# board1-0.net
KiCad netlist of a schematic drawn in EAGLE
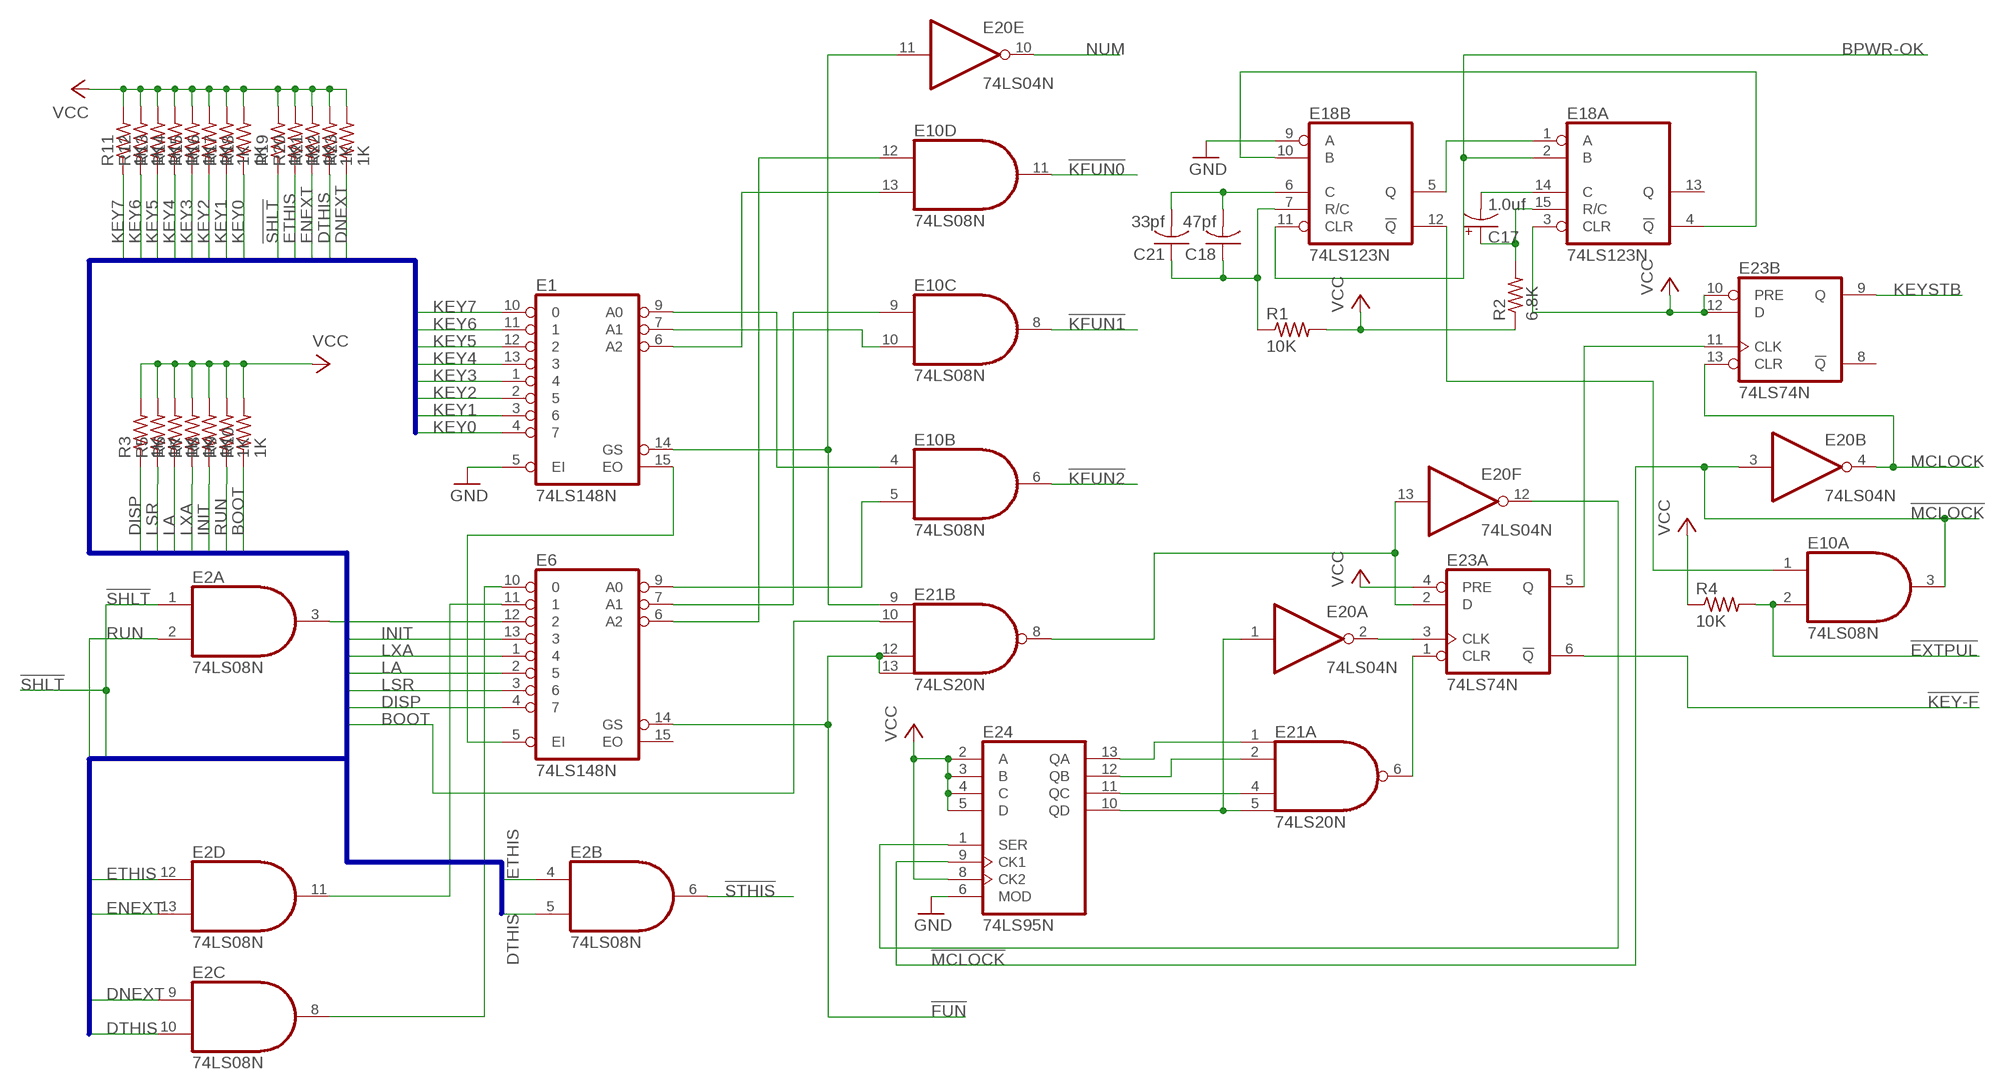
[diagram p0: schematic, sheet 1]
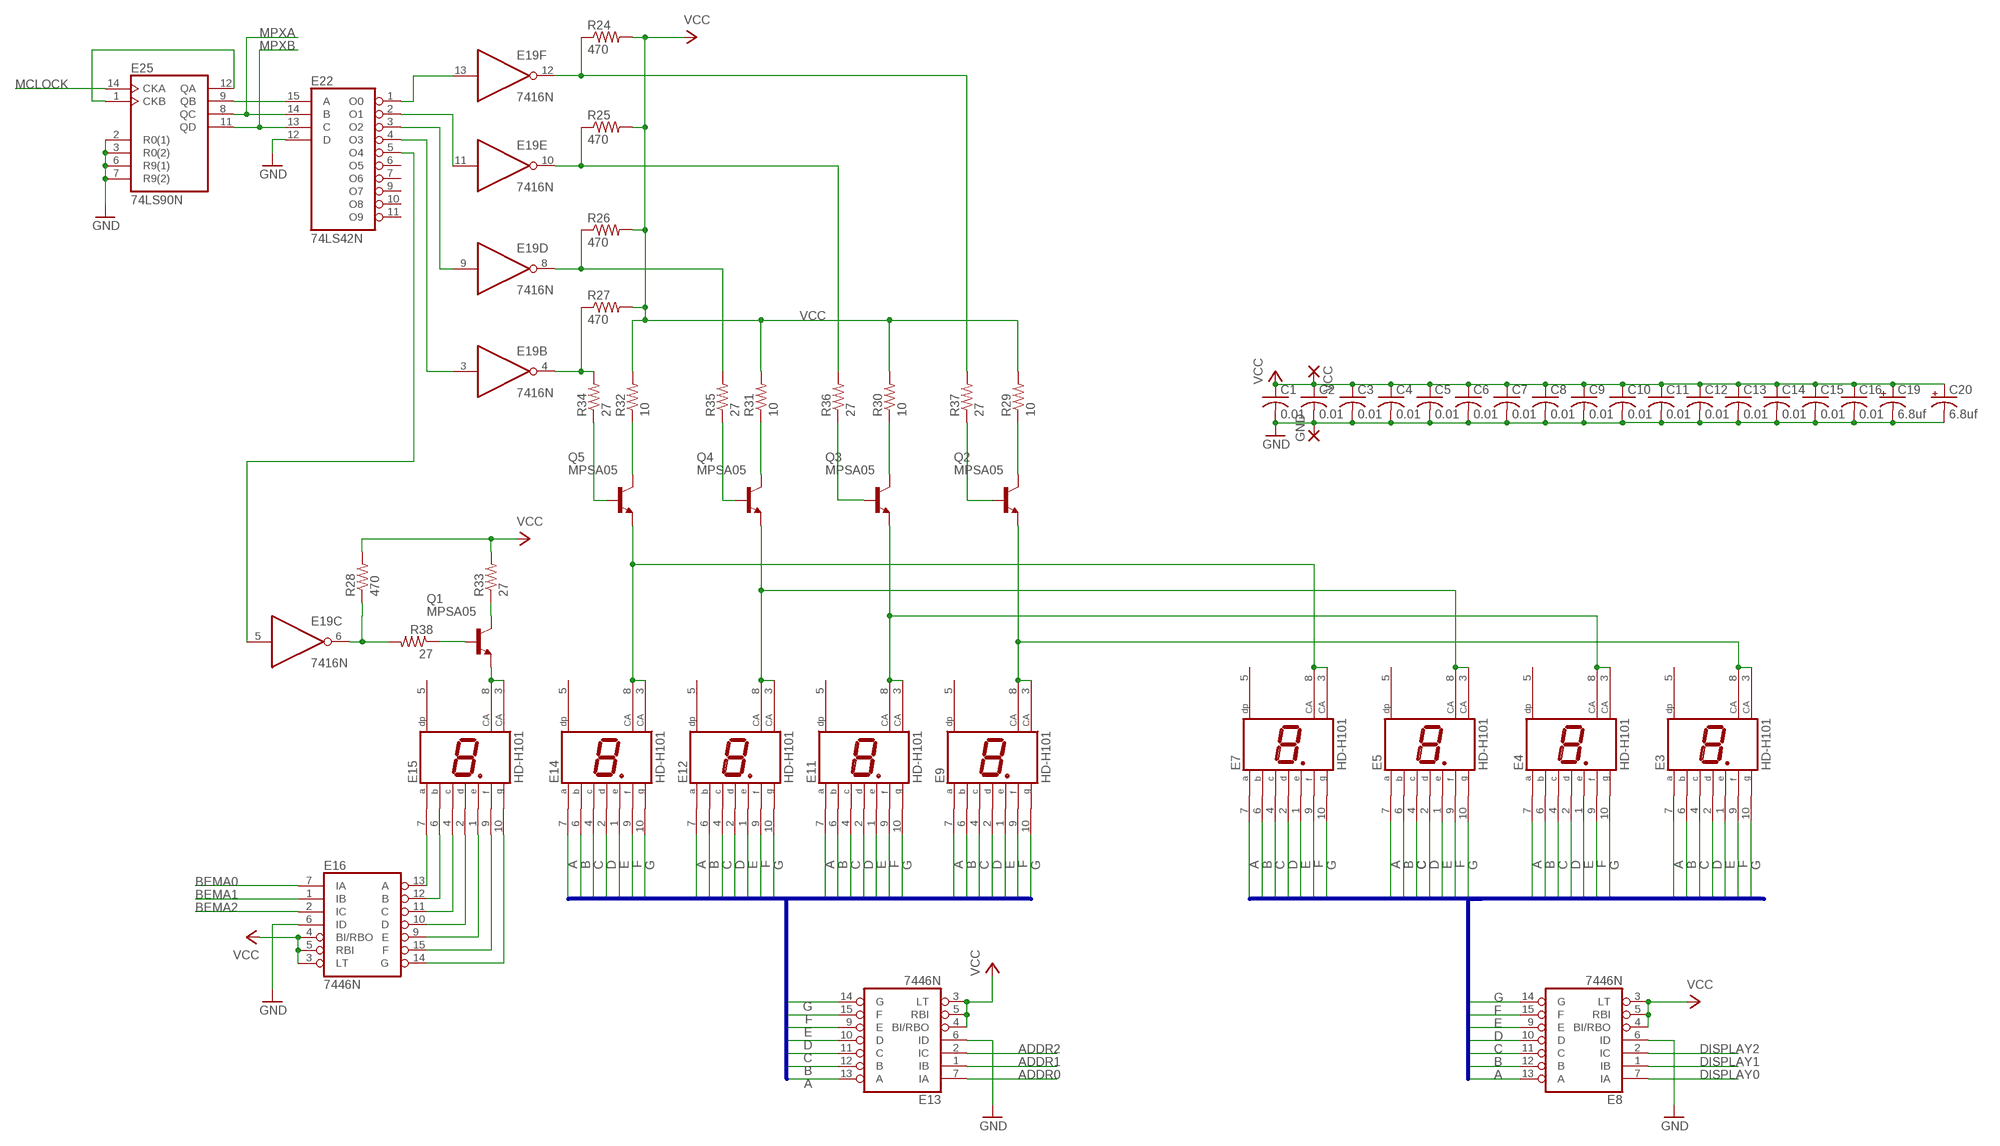
[diagram p1: schematic, sheet 2]
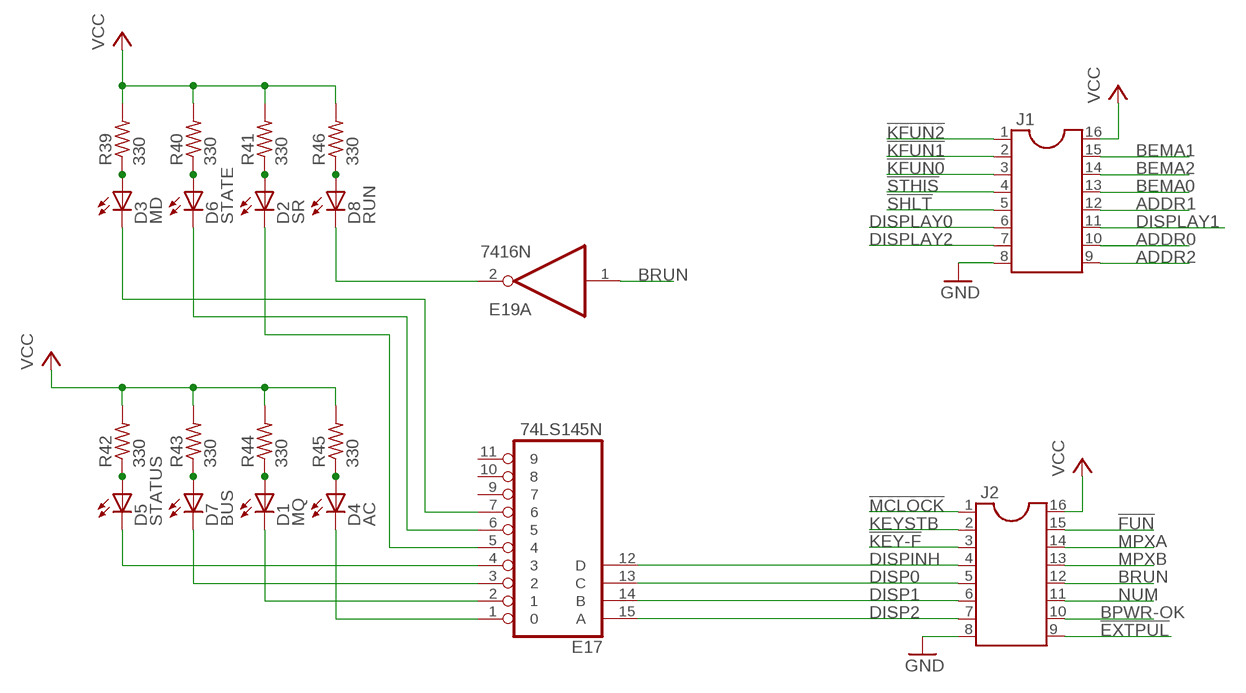
[diagram p2: schematic, sheet 3]
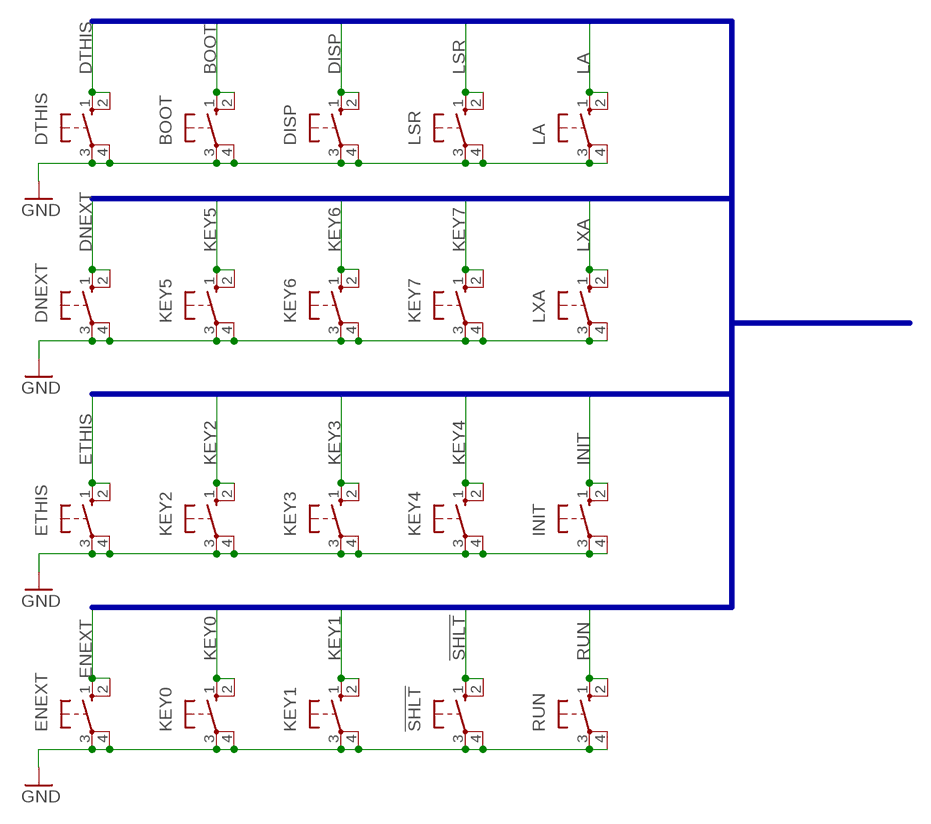
[diagram p3: schematic, sheet 4]

(export (version "E")
  (design (tool "Eeschema 10.0.6"))
  (components
    (comp (ref "!SHLT")
      (value "40-XX")
      (footprint "eagle-import:B3F-40XX")
      (fields (field (name "MF") "OMRON COMPONENTS USA") (field (name "MPN") "B3F-4000"))
      (libsource (lib "eagle-import") (part "40-XX"))
    )
    (comp (ref "BOOT")
      (value "40-XX")
      (footprint "eagle-import:B3F-40XX")
      (fields (field (name "MF") "OMRON COMPONENTS USA") (field (name "MPN") "B3F-4000"))
      (libsource (lib "eagle-import") (part "40-XX"))
    )
    (comp (ref "DISP")
      (value "40-XX")
      (footprint "eagle-import:B3F-40XX")
      (fields (field (name "MF") "OMRON COMPONENTS USA") (field (name "MPN") "B3F-4000"))
      (libsource (lib "eagle-import") (part "40-XX"))
    )
    (comp (ref "DNEXT")
      (value "40-XX")
      (footprint "eagle-import:B3F-40XX")
      (fields (field (name "MF") "OMRON COMPONENTS USA") (field (name "MPN") "B3F-4000"))
      (libsource (lib "eagle-import") (part "40-XX"))
    )
    (comp (ref "DTHIS")
      (value "40-XX")
      (footprint "eagle-import:B3F-40XX")
      (fields (field (name "MF") "OMRON COMPONENTS USA") (field (name "MPN") "B3F-4000"))
      (libsource (lib "eagle-import") (part "40-XX"))
    )
    (comp (ref "ENEXT")
      (value "40-XX")
      (footprint "eagle-import:B3F-40XX")
      (fields (field (name "MF") "OMRON COMPONENTS USA") (field (name "MPN") "B3F-4000"))
      (libsource (lib "eagle-import") (part "40-XX"))
    )
    (comp (ref "ETHIS")
      (value "40-XX")
      (footprint "eagle-import:B3F-40XX")
      (fields (field (name "MF") "OMRON COMPONENTS USA") (field (name "MPN") "B3F-4000"))
      (libsource (lib "eagle-import") (part "40-XX"))
    )
    (comp (ref "INIT")
      (value "40-XX")
      (footprint "eagle-import:B3F-40XX")
      (fields (field (name "MF") "OMRON COMPONENTS USA") (field (name "MPN") "B3F-4000"))
      (libsource (lib "eagle-import") (part "40-XX"))
    )
    (comp (ref "KEY0")
      (value "40-XX")
      (footprint "eagle-import:B3F-40XX")
      (fields (field (name "MF") "OMRON COMPONENTS USA") (field (name "MPN") "B3F-4000"))
      (libsource (lib "eagle-import") (part "40-XX"))
    )
    (comp (ref "KEY1")
      (value "40-XX")
      (footprint "eagle-import:B3F-40XX")
      (fields (field (name "MF") "OMRON COMPONENTS USA") (field (name "MPN") "B3F-4000"))
      (libsource (lib "eagle-import") (part "40-XX"))
    )
    (comp (ref "KEY2")
      (value "40-XX")
      (footprint "eagle-import:B3F-40XX")
      (fields (field (name "MF") "OMRON COMPONENTS USA") (field (name "MPN") "B3F-4000"))
      (libsource (lib "eagle-import") (part "40-XX"))
    )
    (comp (ref "KEY3")
      (value "40-XX")
      (footprint "eagle-import:B3F-40XX")
      (fields (field (name "MF") "OMRON COMPONENTS USA") (field (name "MPN") "B3F-4000"))
      (libsource (lib "eagle-import") (part "40-XX"))
    )
    (comp (ref "KEY4")
      (value "40-XX")
      (footprint "eagle-import:B3F-40XX")
      (fields (field (name "MF") "OMRON COMPONENTS USA") (field (name "MPN") "B3F-4000"))
      (libsource (lib "eagle-import") (part "40-XX"))
    )
    (comp (ref "KEY5")
      (value "40-XX")
      (footprint "eagle-import:B3F-40XX")
      (fields (field (name "MF") "OMRON COMPONENTS USA") (field (name "MPN") "B3F-4000"))
      (libsource (lib "eagle-import") (part "40-XX"))
    )
    (comp (ref "KEY6")
      (value "40-XX")
      (footprint "eagle-import:B3F-40XX")
      (fields (field (name "MF") "OMRON COMPONENTS USA") (field (name "MPN") "B3F-4000"))
      (libsource (lib "eagle-import") (part "40-XX"))
    )
    (comp (ref "KEY7")
      (value "40-XX")
      (footprint "eagle-import:B3F-40XX")
      (fields (field (name "MF") "OMRON COMPONENTS USA") (field (name "MPN") "B3F-4000"))
      (libsource (lib "eagle-import") (part "40-XX"))
    )
    (comp (ref "LA")
      (value "40-XX")
      (footprint "eagle-import:B3F-40XX")
      (fields (field (name "MF") "OMRON COMPONENTS USA") (field (name "MPN") "B3F-4000"))
      (libsource (lib "eagle-import") (part "40-XX"))
    )
    (comp (ref "LSR")
      (value "40-XX")
      (footprint "eagle-import:B3F-40XX")
      (fields (field (name "MF") "OMRON COMPONENTS USA") (field (name "MPN") "B3F-4000"))
      (libsource (lib "eagle-import") (part "40-XX"))
    )
    (comp (ref "LXA")
      (value "40-XX")
      (footprint "eagle-import:B3F-40XX")
      (fields (field (name "MF") "OMRON COMPONENTS USA") (field (name "MPN") "B3F-4000"))
      (libsource (lib "eagle-import") (part "40-XX"))
    )
    (comp (ref "RUN")
      (value "40-XX")
      (footprint "eagle-import:B3F-40XX")
      (fields (field (name "MF") "OMRON COMPONENTS USA") (field (name "MPN") "B3F-4000"))
      (libsource (lib "eagle-import") (part "40-XX"))
    )
    (comp (ref "D1")
      (value "MQ")
      (footprint "eagle-import:LED5MM")
      (libsource (lib "eagle-import") (part "LED5MM"))
    )
    (comp (ref "D2")
      (value "SR")
      (footprint "eagle-import:LED5MM")
      (libsource (lib "eagle-import") (part "LED5MM"))
    )
    (comp (ref "D3")
      (value "MD")
      (footprint "eagle-import:LED5MM")
      (libsource (lib "eagle-import") (part "LED5MM"))
    )
    (comp (ref "D4")
      (value "AC")
      (footprint "eagle-import:LED5MM")
      (libsource (lib "eagle-import") (part "LED5MM"))
    )
    (comp (ref "D5")
      (value "STATUS")
      (footprint "eagle-import:LED5MM")
      (libsource (lib "eagle-import") (part "LED5MM"))
    )
    (comp (ref "D6")
      (value "STATE")
      (footprint "eagle-import:LED5MM")
      (libsource (lib "eagle-import") (part "LED5MM"))
    )
    (comp (ref "D7")
      (value "BUS")
      (footprint "eagle-import:LED5MM")
      (libsource (lib "eagle-import") (part "LED5MM"))
    )
    (comp (ref "D8")
      (value "RUN")
      (footprint "eagle-import:LED5MM")
      (libsource (lib "eagle-import") (part "LED5MM"))
    )
    (comp (ref "E17")
      (value "74LS145N")
      (footprint "eagle-import:DIL16")
      (libsource (lib "eagle-import") (part "74145NLS"))
    )
    (comp (ref "E19")
      (value "7416N")
      (footprint "eagle-import:DIL14")
      (libsource (lib "eagle-import") (part "7416N"))
    )
    (comp (ref "J1")
      (value "DIL16S")
      (footprint "eagle-import:SOCKET-16")
      (libsource (lib "eagle-import") (part "DIL16S"))
    )
    (comp (ref "J2")
      (value "DIL16S")
      (footprint "eagle-import:SOCKET-16")
      (libsource (lib "eagle-import") (part "DIL16S"))
    )
    (comp (ref "R39")
      (value "330")
      (footprint "eagle-import:0207_10")
      (libsource (lib "eagle-import") (part "R-US_0207/10"))
    )
    (comp (ref "R40")
      (value "330")
      (footprint "eagle-import:0207_10")
      (libsource (lib "eagle-import") (part "R-US_0207/10"))
    )
    (comp (ref "R41")
      (value "330")
      (footprint "eagle-import:0207_10")
      (libsource (lib "eagle-import") (part "R-US_0207/10"))
    )
    (comp (ref "R42")
      (value "330")
      (footprint "eagle-import:0207_10")
      (libsource (lib "eagle-import") (part "R-US_0207/10"))
    )
    (comp (ref "R43")
      (value "330")
      (footprint "eagle-import:0207_10")
      (libsource (lib "eagle-import") (part "R-US_0207/10"))
    )
    (comp (ref "R44")
      (value "330")
      (footprint "eagle-import:0207_10")
      (libsource (lib "eagle-import") (part "R-US_0207/10"))
    )
    (comp (ref "R45")
      (value "330")
      (footprint "eagle-import:0207_10")
      (libsource (lib "eagle-import") (part "R-US_0207/10"))
    )
    (comp (ref "R46")
      (value "330")
      (footprint "eagle-import:0207_10")
      (libsource (lib "eagle-import") (part "R-US_0207/10"))
    )
    (comp (ref "C17")
      (value "1.0uf")
      (footprint "eagle-import:E15-5")
      (libsource (lib "eagle-import") (part "CPOL-USE15-5AXIAL"))
    )
    (comp (ref "C18")
      (value "47pf")
      (footprint "eagle-import:C050-025X075")
      (libsource (lib "eagle-import") (part "C-US050-025X075"))
    )
    (comp (ref "C21")
      (value "33pf")
      (footprint "eagle-import:C050-025X075")
      (libsource (lib "eagle-import") (part "C-US050-025X075"))
    )
    (comp (ref "E1")
      (value "74LS148N")
      (footprint "eagle-import:DIL16")
      (libsource (lib "eagle-import") (part "74148NLS"))
    )
    (comp (ref "E2")
      (value "74LS08N")
      (footprint "eagle-import:DIL14")
      (libsource (lib "eagle-import") (part "7408NLS"))
    )
    (comp (ref "E6")
      (value "74LS148N")
      (footprint "eagle-import:DIL16")
      (libsource (lib "eagle-import") (part "74148NLS"))
    )
    (comp (ref "E10")
      (value "74LS08N")
      (footprint "eagle-import:DIL14")
      (libsource (lib "eagle-import") (part "7408NLS"))
    )
    (comp (ref "E18")
      (value "74LS123N")
      (footprint "eagle-import:DIL16")
      (libsource (lib "eagle-import") (part "74123NLS"))
    )
    (comp (ref "E20")
      (value "74LS04N")
      (footprint "eagle-import:DIL14")
      (libsource (lib "eagle-import") (part "7404NLS"))
    )
    (comp (ref "E21")
      (value "74LS20N")
      (footprint "eagle-import:DIL14")
      (libsource (lib "eagle-import") (part "7420NLS"))
    )
    (comp (ref "E23")
      (value "74LS74N")
      (footprint "eagle-import:DIL14")
      (libsource (lib "eagle-import") (part "7474NLS"))
    )
    (comp (ref "E24")
      (value "74LS95N")
      (footprint "eagle-import:DIL14")
      (libsource (lib "eagle-import") (part "7495NLS"))
    )
    (comp (ref "R1")
      (value "10K")
      (footprint "eagle-import:0207_10")
      (libsource (lib "eagle-import") (part "R-US_0207/10"))
    )
    (comp (ref "R2")
      (value "6.8K")
      (footprint "eagle-import:0207_10")
      (libsource (lib "eagle-import") (part "R-US_0207/10"))
    )
    (comp (ref "R3")
      (value "1K")
      (footprint "eagle-import:0207_10")
      (libsource (lib "eagle-import") (part "R-US_0207/10"))
    )
    (comp (ref "R4")
      (value "10K")
      (footprint "eagle-import:0207_10")
      (libsource (lib "eagle-import") (part "R-US_0207/10"))
    )
    (comp (ref "R5")
      (value "1K")
      (footprint "eagle-import:0207_10")
      (libsource (lib "eagle-import") (part "R-US_0207/10"))
    )
    (comp (ref "R6")
      (value "1K")
      (footprint "eagle-import:0207_10")
      (libsource (lib "eagle-import") (part "R-US_0207/10"))
    )
    (comp (ref "R7")
      (value "1K")
      (footprint "eagle-import:0207_10")
      (libsource (lib "eagle-import") (part "R-US_0207/10"))
    )
    (comp (ref "R8")
      (value "1K")
      (footprint "eagle-import:0207_10")
      (libsource (lib "eagle-import") (part "R-US_0207/10"))
    )
    (comp (ref "R9")
      (value "1K")
      (footprint "eagle-import:0207_10")
      (libsource (lib "eagle-import") (part "R-US_0207/10"))
    )
    (comp (ref "R10")
      (value "1K")
      (footprint "eagle-import:0207_10")
      (libsource (lib "eagle-import") (part "R-US_0207/10"))
    )
    (comp (ref "R11")
      (value "1K")
      (footprint "eagle-import:0207_10")
      (libsource (lib "eagle-import") (part "R-US_0207/10"))
    )
    (comp (ref "R12")
      (value "1K")
      (footprint "eagle-import:0207_10")
      (libsource (lib "eagle-import") (part "R-US_0207/10"))
    )
    (comp (ref "R13")
      (value "1K")
      (footprint "eagle-import:0207_10")
      (libsource (lib "eagle-import") (part "R-US_0207/10"))
    )
    (comp (ref "R14")
      (value "1K")
      (footprint "eagle-import:0207_10")
      (libsource (lib "eagle-import") (part "R-US_0207/10"))
    )
    (comp (ref "R15")
      (value "1K")
      (footprint "eagle-import:0207_10")
      (libsource (lib "eagle-import") (part "R-US_0207/10"))
    )
    (comp (ref "R16")
      (value "1K")
      (footprint "eagle-import:0207_10")
      (libsource (lib "eagle-import") (part "R-US_0207/10"))
    )
    (comp (ref "R17")
      (value "1K")
      (footprint "eagle-import:0207_10")
      (libsource (lib "eagle-import") (part "R-US_0207/10"))
    )
    (comp (ref "R18")
      (value "1K")
      (footprint "eagle-import:0207_10")
      (libsource (lib "eagle-import") (part "R-US_0207/10"))
    )
    (comp (ref "R19")
      (value "1K")
      (footprint "eagle-import:0207_10")
      (libsource (lib "eagle-import") (part "R-US_0207/10"))
    )
    (comp (ref "R20")
      (value "1K")
      (footprint "eagle-import:0207_10")
      (libsource (lib "eagle-import") (part "R-US_0207/10"))
    )
    (comp (ref "R21")
      (value "1K")
      (footprint "eagle-import:0207_10")
      (libsource (lib "eagle-import") (part "R-US_0207/10"))
    )
    (comp (ref "R22")
      (value "1K")
      (footprint "eagle-import:0207_10")
      (libsource (lib "eagle-import") (part "R-US_0207/10"))
    )
    (comp (ref "R23")
      (value "1K")
      (footprint "eagle-import:0207_10")
      (libsource (lib "eagle-import") (part "R-US_0207/10"))
    )
    (comp (ref "C1")
      (value "0.01")
      (footprint "eagle-import:C050-025X075")
      (libsource (lib "eagle-import") (part "C-US050-025X075"))
    )
    (comp (ref "C2")
      (value "0.01")
      (footprint "eagle-import:C050-025X075")
      (libsource (lib "eagle-import") (part "C-US050-025X075"))
    )
    (comp (ref "C3")
      (value "0.01")
      (footprint "eagle-import:C050-025X075")
      (libsource (lib "eagle-import") (part "C-US050-025X075"))
    )
    (comp (ref "C4")
      (value "0.01")
      (footprint "eagle-import:C050-025X075")
      (libsource (lib "eagle-import") (part "C-US050-025X075"))
    )
    (comp (ref "C5")
      (value "0.01")
      (footprint "eagle-import:C050-025X075")
      (libsource (lib "eagle-import") (part "C-US050-025X075"))
    )
    (comp (ref "C6")
      (value "0.01")
      (footprint "eagle-import:C050-025X075")
      (libsource (lib "eagle-import") (part "C-US050-025X075"))
    )
    (comp (ref "C7")
      (value "0.01")
      (footprint "eagle-import:C050-025X075")
      (libsource (lib "eagle-import") (part "C-US050-025X075"))
    )
    (comp (ref "C8")
      (value "0.01")
      (footprint "eagle-import:C050-025X075")
      (libsource (lib "eagle-import") (part "C-US050-025X075"))
    )
    (comp (ref "C9")
      (value "0.01")
      (footprint "eagle-import:C050-025X075")
      (libsource (lib "eagle-import") (part "C-US050-025X075"))
    )
    (comp (ref "C10")
      (value "0.01")
      (footprint "eagle-import:C050-025X075")
      (libsource (lib "eagle-import") (part "C-US050-025X075"))
    )
    (comp (ref "C11")
      (value "0.01")
      (footprint "eagle-import:C050-025X075")
      (libsource (lib "eagle-import") (part "C-US050-025X075"))
    )
    (comp (ref "C12")
      (value "0.01")
      (footprint "eagle-import:C050-025X075")
      (libsource (lib "eagle-import") (part "C-US050-025X075"))
    )
    (comp (ref "C13")
      (value "0.01")
      (footprint "eagle-import:C050-025X075")
      (libsource (lib "eagle-import") (part "C-US050-025X075"))
    )
    (comp (ref "C14")
      (value "0.01")
      (footprint "eagle-import:C050-025X075")
      (libsource (lib "eagle-import") (part "C-US050-025X075"))
    )
    (comp (ref "C15")
      (value "0.01")
      (footprint "eagle-import:C050-025X075")
      (libsource (lib "eagle-import") (part "C-US050-025X075"))
    )
    (comp (ref "C16")
      (value "0.01")
      (footprint "eagle-import:C050-025X075")
      (libsource (lib "eagle-import") (part "C-US050-025X075"))
    )
    (comp (ref "C19")
      (value "6.8uf")
      (footprint "eagle-import:E22-6")
      (libsource (lib "eagle-import") (part "CPOL-USE22-6AXIAL"))
    )
    (comp (ref "C20")
      (value "6.8uf")
      (footprint "eagle-import:E22-6")
      (libsource (lib "eagle-import") (part "CPOL-USE22-6AXIAL"))
    )
    (comp (ref "E3")
      (value "HD-H101")
      (footprint "eagle-import:HDSP-M")
      (libsource (lib "eagle-import") (part "HD-H101"))
    )
    (comp (ref "E4")
      (value "HD-H101")
      (footprint "eagle-import:HDSP-M")
      (libsource (lib "eagle-import") (part "HD-H101"))
    )
    (comp (ref "E5")
      (value "HD-H101")
      (footprint "eagle-import:HDSP-M")
      (libsource (lib "eagle-import") (part "HD-H101"))
    )
    (comp (ref "E7")
      (value "HD-H101")
      (footprint "eagle-import:HDSP-M")
      (libsource (lib "eagle-import") (part "HD-H101"))
    )
    (comp (ref "E8")
      (value "7446N")
      (footprint "eagle-import:DIL16")
      (libsource (lib "eagle-import") (part "7446N"))
    )
    (comp (ref "E9")
      (value "HD-H101")
      (footprint "eagle-import:HDSP-M")
      (libsource (lib "eagle-import") (part "HD-H101"))
    )
    (comp (ref "E11")
      (value "HD-H101")
      (footprint "eagle-import:HDSP-M")
      (libsource (lib "eagle-import") (part "HD-H101"))
    )
    (comp (ref "E12")
      (value "HD-H101")
      (footprint "eagle-import:HDSP-M")
      (libsource (lib "eagle-import") (part "HD-H101"))
    )
    (comp (ref "E13")
      (value "7446N")
      (footprint "eagle-import:DIL16")
      (libsource (lib "eagle-import") (part "7446N"))
    )
    (comp (ref "E14")
      (value "HD-H101")
      (footprint "eagle-import:HDSP-M")
      (libsource (lib "eagle-import") (part "HD-H101"))
    )
    (comp (ref "E15")
      (value "HD-H101")
      (footprint "eagle-import:HDSP-M")
      (libsource (lib "eagle-import") (part "HD-H101"))
    )
    (comp (ref "E16")
      (value "7446N")
      (footprint "eagle-import:DIL16")
      (libsource (lib "eagle-import") (part "7446N"))
    )
    (comp (ref "E22")
      (value "74LS42N")
      (footprint "eagle-import:DIL16")
      (libsource (lib "eagle-import") (part "7442NLS"))
    )
    (comp (ref "E25")
      (value "74LS90N")
      (footprint "eagle-import:DIL14")
      (libsource (lib "eagle-import") (part "7490NLS"))
    )
    (comp (ref "GND")
      (value "3,81/1,4")
      (footprint "eagle-import:3,81_1,4")
      (libsource (lib "eagle-import") (part "3,81/1,4"))
    )
    (comp (ref "Q1")
      (value "MPSA05")
      (footprint "eagle-import:TO18")
      (libsource (lib "eagle-import") (part "2N2222A"))
    )
    (comp (ref "Q2")
      (value "MPSA05")
      (footprint "eagle-import:TO18")
      (libsource (lib "eagle-import") (part "2N2222A"))
    )
    (comp (ref "Q3")
      (value "MPSA05")
      (footprint "eagle-import:TO18")
      (libsource (lib "eagle-import") (part "2N2222A"))
    )
    (comp (ref "Q4")
      (value "MPSA05")
      (footprint "eagle-import:TO18")
      (libsource (lib "eagle-import") (part "2N2222A"))
    )
    (comp (ref "Q5")
      (value "MPSA05")
      (footprint "eagle-import:TO18")
      (libsource (lib "eagle-import") (part "2N2222A"))
    )
    (comp (ref "R24")
      (value "470")
      (footprint "eagle-import:0207_10")
      (libsource (lib "eagle-import") (part "R-US_0207/10"))
    )
    (comp (ref "R25")
      (value "470")
      (footprint "eagle-import:0207_10")
      (libsource (lib "eagle-import") (part "R-US_0207/10"))
    )
    (comp (ref "R26")
      (value "470")
      (footprint "eagle-import:0207_10")
      (libsource (lib "eagle-import") (part "R-US_0207/10"))
    )
    (comp (ref "R27")
      (value "470")
      (footprint "eagle-import:0207_10")
      (libsource (lib "eagle-import") (part "R-US_0207/10"))
    )
    (comp (ref "R28")
      (value "470")
      (footprint "eagle-import:0207_10")
      (libsource (lib "eagle-import") (part "R-US_0207/10"))
    )
    (comp (ref "R29")
      (value "10")
      (footprint "eagle-import:0207_10")
      (libsource (lib "eagle-import") (part "R-US_0207/10"))
    )
    (comp (ref "R30")
      (value "10")
      (footprint "eagle-import:0207_10")
      (libsource (lib "eagle-import") (part "R-US_0207/10"))
    )
    (comp (ref "R31")
      (value "10")
      (footprint "eagle-import:0207_10")
      (libsource (lib "eagle-import") (part "R-US_0207/10"))
    )
    (comp (ref "R32")
      (value "10")
      (footprint "eagle-import:0207_10")
      (libsource (lib "eagle-import") (part "R-US_0207/10"))
    )
    (comp (ref "R33")
      (value "27")
      (footprint "eagle-import:0207_10")
      (libsource (lib "eagle-import") (part "R-US_0207/10"))
    )
    (comp (ref "R34")
      (value "27")
      (footprint "eagle-import:0207_10")
      (libsource (lib "eagle-import") (part "R-US_0207/10"))
    )
    (comp (ref "R35")
      (value "27")
      (footprint "eagle-import:0207_10")
      (libsource (lib "eagle-import") (part "R-US_0207/10"))
    )
    (comp (ref "R36")
      (value "27")
      (footprint "eagle-import:0207_10")
      (libsource (lib "eagle-import") (part "R-US_0207/10"))
    )
    (comp (ref "R37")
      (value "27")
      (footprint "eagle-import:0207_10")
      (libsource (lib "eagle-import") (part "R-US_0207/10"))
    )
    (comp (ref "R38")
      (value "27")
      (footprint "eagle-import:0207_10")
      (libsource (lib "eagle-import") (part "R-US_0207/10"))
    )
    (comp (ref "VCC")
      (value "3,81/1,4")
      (footprint "eagle-import:3,81_1,4")
      (libsource (lib "eagle-import") (part "3,81/1,4"))
    )
  )
  (nets
    (net (code "1") (name "A") (class "Default")
      (node (ref "E11") (pin "7") (pinfunction "A_7") (pintype "passive"))
      (node (ref "E12") (pin "7") (pinfunction "A_7") (pintype "passive"))
      (node (ref "E13") (pin "13") (pinfunction "A_13") (pintype "open_collector"))
      (node (ref "E14") (pin "7") (pinfunction "A_7") (pintype "passive"))
      (node (ref "E3") (pin "7") (pinfunction "A_7") (pintype "passive"))
      (node (ref "E4") (pin "7") (pinfunction "A_7") (pintype "passive"))
      (node (ref "E5") (pin "7") (pinfunction "A_7") (pintype "passive"))
      (node (ref "E7") (pin "7") (pinfunction "A_7") (pintype "passive"))
      (node (ref "E8") (pin "13") (pinfunction "A_13") (pintype "open_collector"))
      (node (ref "E9") (pin "7") (pinfunction "A_7") (pintype "passive"))
    )
    (net (code "2") (name "ADDR0") (class "Default")
      (node (ref "E13") (pin "7") (pinfunction "IA_7") (pintype "input"))
      (node (ref "J1") (pin "10") (pinfunction "10_10") (pintype "passive"))
    )
    (net (code "3") (name "ADDR1") (class "Default")
      (node (ref "E13") (pin "1") (pinfunction "IB_1") (pintype "input"))
      (node (ref "J1") (pin "12") (pinfunction "12_12") (pintype "passive"))
    )
    (net (code "4") (name "ADDR2") (class "Default")
      (node (ref "E13") (pin "2") (pinfunction "IC_2") (pintype "input"))
      (node (ref "J1") (pin "9") (pinfunction "9_9") (pintype "passive"))
    )
    (net (code "5") (name "B") (class "Default")
      (node (ref "E11") (pin "6") (pinfunction "B_6") (pintype "passive"))
      (node (ref "E12") (pin "6") (pinfunction "B_6") (pintype "passive"))
      (node (ref "E13") (pin "12") (pinfunction "B_12") (pintype "open_collector"))
      (node (ref "E14") (pin "6") (pinfunction "B_6") (pintype "passive"))
      (node (ref "E3") (pin "6") (pinfunction "B_6") (pintype "passive"))
      (node (ref "E4") (pin "6") (pinfunction "B_6") (pintype "passive"))
      (node (ref "E5") (pin "6") (pinfunction "B_6") (pintype "passive"))
      (node (ref "E7") (pin "6") (pinfunction "B_6") (pintype "passive"))
      (node (ref "E8") (pin "12") (pinfunction "B_12") (pintype "open_collector"))
      (node (ref "E9") (pin "6") (pinfunction "B_6") (pintype "passive"))
    )
    (net (code "6") (name "BEMA0") (class "Default")
      (node (ref "E16") (pin "7") (pinfunction "IA_7") (pintype "input"))
      (node (ref "J1") (pin "13") (pinfunction "13_13") (pintype "passive"))
    )
    (net (code "7") (name "BEMA1") (class "Default")
      (node (ref "E16") (pin "1") (pinfunction "IB_1") (pintype "input"))
      (node (ref "J1") (pin "15") (pinfunction "15_15") (pintype "passive"))
    )
    (net (code "8") (name "BEMA2") (class "Default")
      (node (ref "E16") (pin "2") (pinfunction "IC_2") (pintype "input"))
      (node (ref "J1") (pin "14") (pinfunction "14_14") (pintype "passive"))
    )
    (net (code "9") (name "BOOT") (class "Default")
      (node (ref "BOOT") (pin "1") (pinfunction "S_1") (pintype "passive"))
      (node (ref "BOOT") (pin "2") (pinfunction "S1_2") (pintype "passive"))
      (node (ref "E21") (pin "10") (pinfunction "I1_10") (pintype "input"))
      (node (ref "R10") (pin "1") (pinfunction "1_1") (pintype "passive"))
    )
    (net (code "10") (name "BPWR-OK") (class "Default")
      (node (ref "E18") (pin "11") (pinfunction "CLR_11") (pintype "input"))
      (node (ref "E18") (pin "2") (pinfunction "B_2") (pintype "input"))
      (node (ref "J2") (pin "10") (pinfunction "10_10") (pintype "passive"))
    )
    (net (code "11") (name "BRUN") (class "Default")
      (node (ref "E19") (pin "1") (pinfunction "I_1") (pintype "input"))
      (node (ref "J2") (pin "12") (pinfunction "12_12") (pintype "passive"))
    )
    (net (code "12") (name "C") (class "Default")
      (node (ref "E11") (pin "4") (pinfunction "C_4") (pintype "passive"))
      (node (ref "E12") (pin "4") (pinfunction "C_4") (pintype "passive"))
      (node (ref "E13") (pin "11") (pinfunction "C_11") (pintype "open_collector"))
      (node (ref "E14") (pin "4") (pinfunction "C_4") (pintype "passive"))
      (node (ref "E3") (pin "4") (pinfunction "C_4") (pintype "passive"))
      (node (ref "E4") (pin "4") (pinfunction "C_4") (pintype "passive"))
      (node (ref "E5") (pin "4") (pinfunction "C_4") (pintype "passive"))
      (node (ref "E7") (pin "4") (pinfunction "C_4") (pintype "passive"))
      (node (ref "E8") (pin "11") (pinfunction "C_11") (pintype "open_collector"))
      (node (ref "E9") (pin "4") (pinfunction "C_4") (pintype "passive"))
    )
    (net (code "13") (name "D") (class "Default")
      (node (ref "E11") (pin "2") (pinfunction "D_2") (pintype "passive"))
      (node (ref "E12") (pin "2") (pinfunction "D_2") (pintype "passive"))
      (node (ref "E13") (pin "10") (pinfunction "D_10") (pintype "open_collector"))
      (node (ref "E14") (pin "2") (pinfunction "D_2") (pintype "passive"))
      (node (ref "E3") (pin "2") (pinfunction "D_2") (pintype "passive"))
      (node (ref "E4") (pin "2") (pinfunction "D_2") (pintype "passive"))
      (node (ref "E5") (pin "2") (pinfunction "D_2") (pintype "passive"))
      (node (ref "E7") (pin "2") (pinfunction "D_2") (pintype "passive"))
      (node (ref "E8") (pin "10") (pinfunction "D_10") (pintype "open_collector"))
      (node (ref "E9") (pin "2") (pinfunction "D_2") (pintype "passive"))
    )
    (net (code "14") (name "DISP") (class "Default")
      (node (ref "DISP") (pin "1") (pinfunction "S_1") (pintype "passive"))
      (node (ref "DISP") (pin "2") (pinfunction "S1_2") (pintype "passive"))
      (node (ref "E6") (pin "4") (pinfunction "7_4") (pintype "input"))
      (node (ref "R3") (pin "1") (pinfunction "1_1") (pintype "passive"))
    )
    (net (code "15") (name "DISP0") (class "Default")
      (node (ref "E17") (pin "13") (pinfunction "C_13") (pintype "input"))
      (node (ref "J2") (pin "5") (pinfunction "5_5") (pintype "passive"))
    )
    (net (code "16") (name "DISP1") (class "Default")
      (node (ref "E17") (pin "14") (pinfunction "B_14") (pintype "input"))
      (node (ref "J2") (pin "6") (pinfunction "6_6") (pintype "passive"))
    )
    (net (code "17") (name "DISP2") (class "Default")
      (node (ref "E17") (pin "15") (pinfunction "A_15") (pintype "input"))
      (node (ref "J2") (pin "7") (pinfunction "7_7") (pintype "passive"))
    )
    (net (code "18") (name "DISPINH") (class "Default")
      (node (ref "E17") (pin "12") (pinfunction "D_12") (pintype "input"))
      (node (ref "J2") (pin "4") (pinfunction "4_4") (pintype "passive"))
    )
    (net (code "19") (name "DISPLAY0") (class "Default")
      (node (ref "E8") (pin "7") (pinfunction "IA_7") (pintype "input"))
      (node (ref "J1") (pin "6") (pinfunction "6_6") (pintype "passive"))
    )
    (net (code "20") (name "DISPLAY1") (class "Default")
      (node (ref "E8") (pin "1") (pinfunction "IB_1") (pintype "input"))
      (node (ref "J1") (pin "11") (pinfunction "11_11") (pintype "passive"))
    )
    (net (code "21") (name "DISPLAY2") (class "Default")
      (node (ref "E8") (pin "2") (pinfunction "IC_2") (pintype "input"))
      (node (ref "J1") (pin "7") (pinfunction "7_7") (pintype "passive"))
    )
    (net (code "22") (name "DNEXT") (class "Default")
      (node (ref "DNEXT") (pin "1") (pinfunction "S_1") (pintype "passive"))
      (node (ref "DNEXT") (pin "2") (pinfunction "S1_2") (pintype "passive"))
      (node (ref "E2") (pin "9") (pinfunction "I0_9") (pintype "input"))
      (node (ref "R23") (pin "1") (pinfunction "1_1") (pintype "passive"))
    )
    (net (code "23") (name "DTHIS") (class "Default")
      (node (ref "DTHIS") (pin "1") (pinfunction "S_1") (pintype "passive"))
      (node (ref "DTHIS") (pin "2") (pinfunction "S1_2") (pintype "passive"))
      (node (ref "E2") (pin "10") (pinfunction "I1_10") (pintype "input"))
      (node (ref "E2") (pin "5") (pinfunction "I1_5") (pintype "input"))
      (node (ref "R22") (pin "1") (pinfunction "1_1") (pintype "passive"))
    )
    (net (code "24") (name "E") (class "Default")
      (node (ref "E11") (pin "1") (pinfunction "E_1") (pintype "passive"))
      (node (ref "E12") (pin "1") (pinfunction "E_1") (pintype "passive"))
      (node (ref "E13") (pin "9") (pinfunction "E_9") (pintype "open_collector"))
      (node (ref "E14") (pin "1") (pinfunction "E_1") (pintype "passive"))
      (node (ref "E3") (pin "1") (pinfunction "E_1") (pintype "passive"))
      (node (ref "E4") (pin "1") (pinfunction "E_1") (pintype "passive"))
      (node (ref "E5") (pin "1") (pinfunction "E_1") (pintype "passive"))
      (node (ref "E7") (pin "1") (pinfunction "E_1") (pintype "passive"))
      (node (ref "E8") (pin "9") (pinfunction "E_9") (pintype "open_collector"))
      (node (ref "E9") (pin "1") (pinfunction "E_1") (pintype "passive"))
    )
    (net (code "25") (name "ENEXT") (class "Default")
      (node (ref "E2") (pin "13") (pinfunction "I1_13") (pintype "input"))
      (node (ref "ENEXT") (pin "1") (pinfunction "S_1") (pintype "passive"))
      (node (ref "ENEXT") (pin "2") (pinfunction "S1_2") (pintype "passive"))
      (node (ref "R21") (pin "1") (pinfunction "1_1") (pintype "passive"))
    )
    (net (code "26") (name "ETHIS") (class "Default")
      (node (ref "E2") (pin "12") (pinfunction "I0_12") (pintype "input"))
      (node (ref "E2") (pin "4") (pinfunction "I0_4") (pintype "input"))
      (node (ref "ETHIS") (pin "1") (pinfunction "S_1") (pintype "passive"))
      (node (ref "ETHIS") (pin "2") (pinfunction "S1_2") (pintype "passive"))
      (node (ref "R20") (pin "1") (pinfunction "1_1") (pintype "passive"))
    )
    (net (code "27") (name "F") (class "Default")
      (node (ref "E11") (pin "9") (pinfunction "F_9") (pintype "passive"))
      (node (ref "E12") (pin "9") (pinfunction "F_9") (pintype "passive"))
      (node (ref "E13") (pin "15") (pinfunction "F_15") (pintype "open_collector"))
      (node (ref "E14") (pin "9") (pinfunction "F_9") (pintype "passive"))
      (node (ref "E3") (pin "9") (pinfunction "F_9") (pintype "passive"))
      (node (ref "E4") (pin "9") (pinfunction "F_9") (pintype "passive"))
      (node (ref "E5") (pin "9") (pinfunction "F_9") (pintype "passive"))
      (node (ref "E7") (pin "9") (pinfunction "F_9") (pintype "passive"))
      (node (ref "E8") (pin "15") (pinfunction "F_15") (pintype "open_collector"))
      (node (ref "E9") (pin "9") (pinfunction "F_9") (pintype "passive"))
    )
    (net (code "28") (name "G") (class "Default")
      (node (ref "E11") (pin "10") (pinfunction "G_10") (pintype "passive"))
      (node (ref "E12") (pin "10") (pinfunction "G_10") (pintype "passive"))
      (node (ref "E13") (pin "14") (pinfunction "G_14") (pintype "open_collector"))
      (node (ref "E14") (pin "10") (pinfunction "G_10") (pintype "passive"))
      (node (ref "E3") (pin "10") (pinfunction "G_10") (pintype "passive"))
      (node (ref "E4") (pin "10") (pinfunction "G_10") (pintype "passive"))
      (node (ref "E5") (pin "10") (pinfunction "G_10") (pintype "passive"))
      (node (ref "E7") (pin "10") (pinfunction "G_10") (pintype "passive"))
      (node (ref "E8") (pin "14") (pinfunction "G_14") (pintype "open_collector"))
      (node (ref "E9") (pin "10") (pinfunction "G_10") (pintype "passive"))
    )
    (net (code "29") (name "GND") (class "Default")
      (node (ref "!SHLT") (pin "3") (pinfunction "P_3") (pintype "passive"))
      (node (ref "!SHLT") (pin "4") (pinfunction "P1_4") (pintype "passive"))
      (node (ref "BOOT") (pin "3") (pinfunction "P_3") (pintype "passive"))
      (node (ref "BOOT") (pin "4") (pinfunction "P1_4") (pintype "passive"))
      (node (ref "C1") (pin "2") (pinfunction "2_2") (pintype "passive"))
      (node (ref "C10") (pin "2") (pinfunction "2_2") (pintype "passive"))
      (node (ref "C11") (pin "2") (pinfunction "2_2") (pintype "passive"))
      (node (ref "C12") (pin "2") (pinfunction "2_2") (pintype "passive"))
      (node (ref "C13") (pin "2") (pinfunction "2_2") (pintype "passive"))
      (node (ref "C14") (pin "2") (pinfunction "2_2") (pintype "passive"))
      (node (ref "C15") (pin "2") (pinfunction "2_2") (pintype "passive"))
      (node (ref "C16") (pin "2") (pinfunction "2_2") (pintype "passive"))
      (node (ref "C19") (pin "-") (pinfunction "-_-") (pintype "passive"))
      (node (ref "C2") (pin "2") (pinfunction "2_2") (pintype "passive"))
      (node (ref "C20") (pin "-") (pinfunction "-_-") (pintype "passive"))
      (node (ref "C3") (pin "2") (pinfunction "2_2") (pintype "passive"))
      (node (ref "C4") (pin "2") (pinfunction "2_2") (pintype "passive"))
      (node (ref "C5") (pin "2") (pinfunction "2_2") (pintype "passive"))
      (node (ref "C6") (pin "2") (pinfunction "2_2") (pintype "passive"))
      (node (ref "C7") (pin "2") (pinfunction "2_2") (pintype "passive"))
      (node (ref "C8") (pin "2") (pinfunction "2_2") (pintype "passive"))
      (node (ref "C9") (pin "2") (pinfunction "2_2") (pintype "passive"))
      (node (ref "DISP") (pin "3") (pinfunction "P_3") (pintype "passive"))
      (node (ref "DISP") (pin "4") (pinfunction "P1_4") (pintype "passive"))
      (node (ref "DNEXT") (pin "3") (pinfunction "P_3") (pintype "passive"))
      (node (ref "DNEXT") (pin "4") (pinfunction "P1_4") (pintype "passive"))
      (node (ref "DTHIS") (pin "3") (pinfunction "P_3") (pintype "passive"))
      (node (ref "DTHIS") (pin "4") (pinfunction "P1_4") (pintype "passive"))
      (node (ref "E1") (pin "5") (pinfunction "EI_5") (pintype "input"))
      (node (ref "E13") (pin "6") (pinfunction "ID_6") (pintype "input"))
      (node (ref "E16") (pin "6") (pinfunction "ID_6") (pintype "input"))
      (node (ref "E18") (pin "9") (pinfunction "A_9") (pintype "input"))
      (node (ref "E22") (pin "12") (pinfunction "D_12") (pintype "input"))
      (node (ref "E24") (pin "6") (pinfunction "MOD_6") (pintype "input"))
      (node (ref "E25") (pin "2") (pinfunction "R0(1)_2") (pintype "input"))
      (node (ref "E25") (pin "3") (pinfunction "R0(2)_3") (pintype "input"))
      (node (ref "E25") (pin "6") (pinfunction "R9(1)_6") (pintype "input"))
      (node (ref "E25") (pin "7") (pinfunction "R9(2)_7") (pintype "input"))
      (node (ref "E8") (pin "6") (pinfunction "ID_6") (pintype "input"))
      (node (ref "ENEXT") (pin "3") (pinfunction "P_3") (pintype "passive"))
      (node (ref "ENEXT") (pin "4") (pinfunction "P1_4") (pintype "passive"))
      (node (ref "ETHIS") (pin "3") (pinfunction "P_3") (pintype "passive"))
      (node (ref "ETHIS") (pin "4") (pinfunction "P1_4") (pintype "passive"))
      (node (ref "GND") (pin "1") (pinfunction "P_1") (pintype "passive"))
      (node (ref "INIT") (pin "3") (pinfunction "P_3") (pintype "passive"))
      (node (ref "INIT") (pin "4") (pinfunction "P1_4") (pintype "passive"))
      (node (ref "J1") (pin "8") (pinfunction "8_8") (pintype "passive"))
      (node (ref "J2") (pin "8") (pinfunction "8_8") (pintype "passive"))
      (node (ref "KEY0") (pin "3") (pinfunction "P_3") (pintype "passive"))
      (node (ref "KEY0") (pin "4") (pinfunction "P1_4") (pintype "passive"))
      (node (ref "KEY1") (pin "3") (pinfunction "P_3") (pintype "passive"))
      (node (ref "KEY1") (pin "4") (pinfunction "P1_4") (pintype "passive"))
      (node (ref "KEY2") (pin "3") (pinfunction "P_3") (pintype "passive"))
      (node (ref "KEY2") (pin "4") (pinfunction "P1_4") (pintype "passive"))
      (node (ref "KEY3") (pin "3") (pinfunction "P_3") (pintype "passive"))
      (node (ref "KEY3") (pin "4") (pinfunction "P1_4") (pintype "passive"))
      (node (ref "KEY4") (pin "3") (pinfunction "P_3") (pintype "passive"))
      (node (ref "KEY4") (pin "4") (pinfunction "P1_4") (pintype "passive"))
      (node (ref "KEY5") (pin "3") (pinfunction "P_3") (pintype "passive"))
      (node (ref "KEY5") (pin "4") (pinfunction "P1_4") (pintype "passive"))
      (node (ref "KEY6") (pin "3") (pinfunction "P_3") (pintype "passive"))
      (node (ref "KEY6") (pin "4") (pinfunction "P1_4") (pintype "passive"))
      (node (ref "KEY7") (pin "3") (pinfunction "P_3") (pintype "passive"))
      (node (ref "KEY7") (pin "4") (pinfunction "P1_4") (pintype "passive"))
      (node (ref "LA") (pin "3") (pinfunction "P_3") (pintype "passive"))
      (node (ref "LA") (pin "4") (pinfunction "P1_4") (pintype "passive"))
      (node (ref "LSR") (pin "3") (pinfunction "P_3") (pintype "passive"))
      (node (ref "LSR") (pin "4") (pinfunction "P1_4") (pintype "passive"))
      (node (ref "LXA") (pin "3") (pinfunction "P_3") (pintype "passive"))
      (node (ref "LXA") (pin "4") (pinfunction "P1_4") (pintype "passive"))
      (node (ref "RUN") (pin "3") (pinfunction "P_3") (pintype "passive"))
      (node (ref "RUN") (pin "4") (pinfunction "P1_4") (pintype "passive"))
    )
    (net (code "30") (name "INIT") (class "Default")
      (node (ref "E6") (pin "13") (pinfunction "3_13") (pintype "input"))
      (node (ref "INIT") (pin "1") (pinfunction "S_1") (pintype "passive"))
      (node (ref "INIT") (pin "2") (pinfunction "S1_2") (pintype "passive"))
      (node (ref "R8") (pin "1") (pinfunction "1_1") (pintype "passive"))
    )
    (net (code "31") (name "KEY0") (class "Default")
      (node (ref "E1") (pin "4") (pinfunction "7_4") (pintype "input"))
      (node (ref "KEY0") (pin "1") (pinfunction "S_1") (pintype "passive"))
      (node (ref "KEY0") (pin "2") (pinfunction "S1_2") (pintype "passive"))
      (node (ref "R18") (pin "1") (pinfunction "1_1") (pintype "passive"))
    )
    (net (code "32") (name "KEY1") (class "Default")
      (node (ref "E1") (pin "3") (pinfunction "6_3") (pintype "input"))
      (node (ref "KEY1") (pin "1") (pinfunction "S_1") (pintype "passive"))
      (node (ref "KEY1") (pin "2") (pinfunction "S1_2") (pintype "passive"))
      (node (ref "R17") (pin "1") (pinfunction "1_1") (pintype "passive"))
    )
    (net (code "33") (name "KEY2") (class "Default")
      (node (ref "E1") (pin "2") (pinfunction "5_2") (pintype "input"))
      (node (ref "KEY2") (pin "1") (pinfunction "S_1") (pintype "passive"))
      (node (ref "KEY2") (pin "2") (pinfunction "S1_2") (pintype "passive"))
      (node (ref "R16") (pin "1") (pinfunction "1_1") (pintype "passive"))
    )
    (net (code "34") (name "KEY3") (class "Default")
      (node (ref "E1") (pin "1") (pinfunction "4_1") (pintype "input"))
      (node (ref "KEY3") (pin "1") (pinfunction "S_1") (pintype "passive"))
      (node (ref "KEY3") (pin "2") (pinfunction "S1_2") (pintype "passive"))
      (node (ref "R15") (pin "1") (pinfunction "1_1") (pintype "passive"))
    )
    (net (code "35") (name "KEY4") (class "Default")
      (node (ref "E1") (pin "13") (pinfunction "3_13") (pintype "input"))
      (node (ref "KEY4") (pin "1") (pinfunction "S_1") (pintype "passive"))
      (node (ref "KEY4") (pin "2") (pinfunction "S1_2") (pintype "passive"))
      (node (ref "R14") (pin "1") (pinfunction "1_1") (pintype "passive"))
    )
    (net (code "36") (name "KEY5") (class "Default")
      (node (ref "E1") (pin "12") (pinfunction "2_12") (pintype "input"))
      (node (ref "KEY5") (pin "1") (pinfunction "S_1") (pintype "passive"))
      (node (ref "KEY5") (pin "2") (pinfunction "S1_2") (pintype "passive"))
      (node (ref "R13") (pin "1") (pinfunction "1_1") (pintype "passive"))
    )
    (net (code "37") (name "KEY6") (class "Default")
      (node (ref "E1") (pin "11") (pinfunction "1_11") (pintype "input"))
      (node (ref "KEY6") (pin "1") (pinfunction "S_1") (pintype "passive"))
      (node (ref "KEY6") (pin "2") (pinfunction "S1_2") (pintype "passive"))
      (node (ref "R12") (pin "1") (pinfunction "1_1") (pintype "passive"))
    )
    (net (code "38") (name "KEY7") (class "Default")
      (node (ref "E1") (pin "10") (pinfunction "0_10") (pintype "input"))
      (node (ref "KEY7") (pin "1") (pinfunction "S_1") (pintype "passive"))
      (node (ref "KEY7") (pin "2") (pinfunction "S1_2") (pintype "passive"))
      (node (ref "R11") (pin "1") (pinfunction "1_1") (pintype "passive"))
    )
    (net (code "39") (name "KEYSTB") (class "Default")
      (node (ref "E23") (pin "9") (pinfunction "Q_9") (pintype "output"))
      (node (ref "J2") (pin "2") (pinfunction "2_2") (pintype "passive"))
    )
    (net (code "40") (name "LA") (class "Default")
      (node (ref "E6") (pin "2") (pinfunction "5_2") (pintype "input"))
      (node (ref "LA") (pin "1") (pinfunction "S_1") (pintype "passive"))
      (node (ref "LA") (pin "2") (pinfunction "S1_2") (pintype "passive"))
      (node (ref "R6") (pin "1") (pinfunction "1_1") (pintype "passive"))
    )
    (net (code "41") (name "LSR") (class "Default")
      (node (ref "E6") (pin "3") (pinfunction "6_3") (pintype "input"))
      (node (ref "LSR") (pin "1") (pinfunction "S_1") (pintype "passive"))
      (node (ref "LSR") (pin "2") (pinfunction "S1_2") (pintype "passive"))
      (node (ref "R5") (pin "1") (pinfunction "1_1") (pintype "passive"))
    )
    (net (code "42") (name "LXA") (class "Default")
      (node (ref "E6") (pin "1") (pinfunction "4_1") (pintype "input"))
      (node (ref "LXA") (pin "1") (pinfunction "S_1") (pintype "passive"))
      (node (ref "LXA") (pin "2") (pinfunction "S1_2") (pintype "passive"))
      (node (ref "R7") (pin "1") (pinfunction "1_1") (pintype "passive"))
    )
    (net (code "43") (name "MCLOCK") (class "Default")
      (node (ref "E20") (pin "4") (pinfunction "O_4") (pintype "output"))
      (node (ref "E23") (pin "13") (pinfunction "CLR_13") (pintype "input"))
      (node (ref "E25") (pin "14") (pinfunction "CKA_14") (pintype "input"))
    )
    (net (code "44") (name "MPXA") (class "Default")
      (node (ref "E22") (pin "14") (pinfunction "B_14") (pintype "input"))
      (node (ref "E25") (pin "8") (pinfunction "QC_8") (pintype "output"))
      (node (ref "J2") (pin "14") (pinfunction "14_14") (pintype "passive"))
    )
    (net (code "45") (name "MPXB") (class "Default")
      (node (ref "E22") (pin "13") (pinfunction "C_13") (pintype "input"))
      (node (ref "E25") (pin "11") (pinfunction "QD_11") (pintype "output"))
      (node (ref "J2") (pin "13") (pinfunction "13_13") (pintype "passive"))
    )
    (net (code "46") (name "NUM") (class "Default")
      (node (ref "E20") (pin "10") (pinfunction "O_10") (pintype "output"))
      (node (ref "J2") (pin "11") (pinfunction "11_11") (pintype "passive"))
    )
    (net (code "47") (name "Net-(D1-C)") (class "Default")
      (node (ref "D1") (pin "K") (pinfunction "C_K") (pintype "passive"))
      (node (ref "E17") (pin "2") (pinfunction "1_2") (pintype "output"))
    )
    (net (code "48") (name "Net-(D1-PadA)") (class "Default")
      (node (ref "D1") (pin "A") (pinfunction "A_A") (pintype "passive"))
      (node (ref "R44") (pin "1") (pinfunction "1_1") (pintype "passive"))
    )
    (net (code "49") (name "Net-(D2-C)") (class "Default")
      (node (ref "D2") (pin "K") (pinfunction "C_K") (pintype "passive"))
      (node (ref "E17") (pin "5") (pinfunction "4_5") (pintype "output"))
    )
    (net (code "50") (name "Net-(D2-PadA)") (class "Default")
      (node (ref "D2") (pin "A") (pinfunction "A_A") (pintype "passive"))
      (node (ref "R41") (pin "1") (pinfunction "1_1") (pintype "passive"))
    )
    (net (code "51") (name "Net-(D3-C)") (class "Default")
      (node (ref "D3") (pin "K") (pinfunction "C_K") (pintype "passive"))
      (node (ref "E17") (pin "7") (pinfunction "6_7") (pintype "output"))
    )
    (net (code "52") (name "Net-(D3-PadA)") (class "Default")
      (node (ref "D3") (pin "A") (pinfunction "A_A") (pintype "passive"))
      (node (ref "R39") (pin "1") (pinfunction "1_1") (pintype "passive"))
    )
    (net (code "53") (name "Net-(D4-C)") (class "Default")
      (node (ref "D4") (pin "K") (pinfunction "C_K") (pintype "passive"))
      (node (ref "E17") (pin "1") (pinfunction "0_1") (pintype "output"))
    )
    (net (code "54") (name "Net-(D4-PadA)") (class "Default")
      (node (ref "D4") (pin "A") (pinfunction "A_A") (pintype "passive"))
      (node (ref "R45") (pin "1") (pinfunction "1_1") (pintype "passive"))
    )
    (net (code "55") (name "Net-(D5-C)") (class "Default")
      (node (ref "D5") (pin "K") (pinfunction "C_K") (pintype "passive"))
      (node (ref "E17") (pin "4") (pinfunction "3_4") (pintype "output"))
    )
    (net (code "56") (name "Net-(D5-PadA)") (class "Default")
      (node (ref "D5") (pin "A") (pinfunction "A_A") (pintype "passive"))
      (node (ref "R42") (pin "1") (pinfunction "1_1") (pintype "passive"))
    )
    (net (code "57") (name "Net-(D6-C)") (class "Default")
      (node (ref "D6") (pin "K") (pinfunction "C_K") (pintype "passive"))
      (node (ref "E17") (pin "6") (pinfunction "5_6") (pintype "output"))
    )
    (net (code "58") (name "Net-(D6-PadA)") (class "Default")
      (node (ref "D6") (pin "A") (pinfunction "A_A") (pintype "passive"))
      (node (ref "R40") (pin "1") (pinfunction "1_1") (pintype "passive"))
    )
    (net (code "59") (name "Net-(D7-C)") (class "Default")
      (node (ref "D7") (pin "K") (pinfunction "C_K") (pintype "passive"))
      (node (ref "E17") (pin "3") (pinfunction "2_3") (pintype "output"))
    )
    (net (code "60") (name "Net-(D7-PadA)") (class "Default")
      (node (ref "D7") (pin "A") (pinfunction "A_A") (pintype "passive"))
      (node (ref "R43") (pin "1") (pinfunction "1_1") (pintype "passive"))
    )
    (net (code "61") (name "Net-(D8-C)") (class "Default")
      (node (ref "D8") (pin "K") (pinfunction "C_K") (pintype "passive"))
      (node (ref "E19") (pin "2") (pinfunction "O_2") (pintype "open_collector"))
    )
    (net (code "62") (name "Net-(D8-PadA)") (class "Default")
      (node (ref "D8") (pin "A") (pinfunction "A_A") (pintype "passive"))
      (node (ref "R46") (pin "1") (pinfunction "1_1") (pintype "passive"))
    )
    (net (code "63") (name "Net-(E1A-EO)") (class "Default")
      (node (ref "E1") (pin "15") (pinfunction "EO_15") (pintype "output"))
      (node (ref "E6") (pin "5") (pinfunction "EI_5") (pintype "input"))
    )
    (net (code "64") (name "Net-(E1A-GS)") (class "Default")
      (node (ref "E1") (pin "14") (pinfunction "GS_14") (pintype "output"))
      (node (ref "E20") (pin "11") (pinfunction "I_11") (pintype "input"))
      (node (ref "E21") (pin "9") (pinfunction "I0_9") (pintype "input"))
    )
    (net (code "65") (name "Net-(E2A-O)") (class "Default")
      (node (ref "E2") (pin "3") (pinfunction "O_3") (pintype "output"))
      (node (ref "E6") (pin "12") (pinfunction "2_12") (pintype "input"))
    )
    (net (code "66") (name "Net-(E2C-O)") (class "Default")
      (node (ref "E2") (pin "8") (pinfunction "O_8") (pintype "output"))
      (node (ref "E6") (pin "10") (pinfunction "0_10") (pintype "input"))
    )
    (net (code "67") (name "Net-(E2D-O)") (class "Default")
      (node (ref "E2") (pin "11") (pinfunction "O_11") (pintype "output"))
      (node (ref "E6") (pin "11") (pinfunction "1_11") (pintype "input"))
    )
    (net (code "68") (name "Net-(E10A-I0)") (class "Default")
      (node (ref "E10") (pin "1") (pinfunction "I0_1") (pintype "input"))
      (node (ref "E18") (pin "12") (pinfunction "~{Q}_12") (pintype "output"))
    )
    (net (code "69") (name "Net-(E10B-I0)") (class "Default")
      (node (ref "E1") (pin "9") (pinfunction "A0_9") (pintype "output"))
      (node (ref "E10") (pin "4") (pinfunction "I0_4") (pintype "input"))
    )
    (net (code "70") (name "Net-(E10B-I1)") (class "Default")
      (node (ref "E10") (pin "5") (pinfunction "I1_5") (pintype "input"))
      (node (ref "E6") (pin "9") (pinfunction "A0_9") (pintype "output"))
    )
    (net (code "71") (name "Net-(E10C-I0)") (class "Default")
      (node (ref "E10") (pin "9") (pinfunction "I0_9") (pintype "input"))
      (node (ref "E6") (pin "7") (pinfunction "A1_7") (pintype "output"))
    )
    (net (code "72") (name "Net-(E10C-I1)") (class "Default")
      (node (ref "E1") (pin "7") (pinfunction "A1_7") (pintype "output"))
      (node (ref "E10") (pin "10") (pinfunction "I1_10") (pintype "input"))
    )
    (net (code "73") (name "Net-(E10D-I0)") (class "Default")
      (node (ref "E10") (pin "12") (pinfunction "I0_12") (pintype "input"))
      (node (ref "E6") (pin "6") (pinfunction "A2_6") (pintype "output"))
    )
    (net (code "74") (name "Net-(E10D-I1)") (class "Default")
      (node (ref "E1") (pin "6") (pinfunction "A2_6") (pintype "output"))
      (node (ref "E10") (pin "13") (pinfunction "I1_13") (pintype "input"))
    )
    (net (code "75") (name "Net-(E15-A)") (class "Default")
      (node (ref "E15") (pin "7") (pinfunction "A_7") (pintype "passive"))
      (node (ref "E16") (pin "13") (pinfunction "A_13") (pintype "open_collector"))
    )
    (net (code "76") (name "Net-(E15-B)") (class "Default")
      (node (ref "E15") (pin "6") (pinfunction "B_6") (pintype "passive"))
      (node (ref "E16") (pin "12") (pinfunction "B_12") (pintype "open_collector"))
    )
    (net (code "77") (name "Net-(E15-C)") (class "Default")
      (node (ref "E15") (pin "4") (pinfunction "C_4") (pintype "passive"))
      (node (ref "E16") (pin "11") (pinfunction "C_11") (pintype "open_collector"))
    )
    (net (code "78") (name "Net-(E15-D)") (class "Default")
      (node (ref "E15") (pin "2") (pinfunction "D_2") (pintype "passive"))
      (node (ref "E16") (pin "10") (pinfunction "D_10") (pintype "open_collector"))
    )
    (net (code "79") (name "Net-(E15-E)") (class "Default")
      (node (ref "E15") (pin "1") (pinfunction "E_1") (pintype "passive"))
      (node (ref "E16") (pin "9") (pinfunction "E_9") (pintype "open_collector"))
    )
    (net (code "80") (name "Net-(E15-F)") (class "Default")
      (node (ref "E15") (pin "9") (pinfunction "F_9") (pintype "passive"))
      (node (ref "E16") (pin "15") (pinfunction "F_15") (pintype "open_collector"))
    )
    (net (code "81") (name "Net-(E15-G)") (class "Default")
      (node (ref "E15") (pin "10") (pinfunction "G_10") (pintype "passive"))
      (node (ref "E16") (pin "14") (pinfunction "G_14") (pintype "open_collector"))
    )
    (net (code "82") (name "Net-(E18A-A)") (class "Default")
      (node (ref "E18") (pin "1") (pinfunction "A_1") (pintype "input"))
      (node (ref "E18") (pin "5") (pinfunction "Q_5") (pintype "output"))
    )
    (net (code "83") (name "Net-(E18A-C)") (class "Default")
      (node (ref "C17") (pin "-") (pinfunction "-_-") (pintype "passive"))
      (node (ref "E18") (pin "14") (pinfunction "C_14") (pintype "input"))
    )
    (net (code "84") (name "Net-(E18A-R{slash}C)") (class "Default")
      (node (ref "C17") (pin "+") (pinfunction "+_+") (pintype "passive"))
      (node (ref "E18") (pin "15") (pinfunction "R/C_15") (pintype "input"))
      (node (ref "R2") (pin "2") (pinfunction "2_2") (pintype "passive"))
    )
    (net (code "85") (name "Net-(E18A-~{Q})") (class "Default")
      (node (ref "E18") (pin "10") (pinfunction "B_10") (pintype "input"))
      (node (ref "E18") (pin "4") (pinfunction "~{Q}_4") (pintype "output"))
    )
    (net (code "86") (name "Net-(E18B-C)") (class "Default")
      (node (ref "C18") (pin "2") (pinfunction "2_2") (pintype "passive"))
      (node (ref "C21") (pin "2") (pinfunction "2_2") (pintype "passive"))
      (node (ref "E18") (pin "6") (pinfunction "C_6") (pintype "input"))
    )
    (net (code "87") (name "Net-(E18B-R{slash}C)") (class "Default")
      (node (ref "C18") (pin "1") (pinfunction "1_1") (pintype "passive"))
      (node (ref "C21") (pin "1") (pinfunction "1_1") (pintype "passive"))
      (node (ref "E18") (pin "7") (pinfunction "R/C_7") (pintype "input"))
      (node (ref "R1") (pin "1") (pinfunction "1_1") (pintype "passive"))
    )
    (net (code "88") (name "Net-(E19B-I)") (class "Default")
      (node (ref "E19") (pin "3") (pinfunction "I_3") (pintype "input"))
      (node (ref "E22") (pin "4") (pinfunction "O3_4") (pintype "output"))
    )
    (net (code "89") (name "Net-(E19B-O)") (class "Default")
      (node (ref "E19") (pin "4") (pinfunction "O_4") (pintype "open_collector"))
      (node (ref "R27") (pin "1") (pinfunction "1_1") (pintype "passive"))
      (node (ref "R34") (pin "2") (pinfunction "2_2") (pintype "passive"))
    )
    (net (code "90") (name "Net-(E19C-I)") (class "Default")
      (node (ref "E19") (pin "5") (pinfunction "I_5") (pintype "input"))
      (node (ref "E22") (pin "5") (pinfunction "O4_5") (pintype "output"))
    )
    (net (code "91") (name "Net-(E19C-O)") (class "Default")
      (node (ref "E19") (pin "6") (pinfunction "O_6") (pintype "open_collector"))
      (node (ref "R28") (pin "1") (pinfunction "1_1") (pintype "passive"))
      (node (ref "R38") (pin "2") (pinfunction "2_2") (pintype "passive"))
    )
    (net (code "92") (name "Net-(E19D-I)") (class "Default")
      (node (ref "E19") (pin "9") (pinfunction "I_9") (pintype "input"))
      (node (ref "E22") (pin "3") (pinfunction "O2_3") (pintype "output"))
    )
    (net (code "93") (name "Net-(E19D-O)") (class "Default")
      (node (ref "E19") (pin "8") (pinfunction "O_8") (pintype "open_collector"))
      (node (ref "R26") (pin "1") (pinfunction "1_1") (pintype "passive"))
      (node (ref "R35") (pin "2") (pinfunction "2_2") (pintype "passive"))
    )
    (net (code "94") (name "Net-(E19E-I)") (class "Default")
      (node (ref "E19") (pin "11") (pinfunction "I_11") (pintype "input"))
      (node (ref "E22") (pin "2") (pinfunction "O1_2") (pintype "output"))
    )
    (net (code "95") (name "Net-(E19E-O)") (class "Default")
      (node (ref "E19") (pin "10") (pinfunction "O_10") (pintype "open_collector"))
      (node (ref "R25") (pin "1") (pinfunction "1_1") (pintype "passive"))
      (node (ref "R36") (pin "2") (pinfunction "2_2") (pintype "passive"))
    )
    (net (code "96") (name "Net-(E19F-I)") (class "Default")
      (node (ref "E19") (pin "13") (pinfunction "I_13") (pintype "input"))
      (node (ref "E22") (pin "1") (pinfunction "O0_1") (pintype "output"))
    )
    (net (code "97") (name "Net-(E19F-O)") (class "Default")
      (node (ref "E19") (pin "12") (pinfunction "O_12") (pintype "open_collector"))
      (node (ref "R24") (pin "1") (pinfunction "1_1") (pintype "passive"))
      (node (ref "R37") (pin "2") (pinfunction "2_2") (pintype "passive"))
    )
    (net (code "98") (name "Net-(E20A-I)") (class "Default")
      (node (ref "E20") (pin "1") (pinfunction "I_1") (pintype "input"))
      (node (ref "E21") (pin "5") (pinfunction "I3_5") (pintype "input"))
      (node (ref "E24") (pin "10") (pinfunction "QD_10") (pintype "output"))
    )
    (net (code "99") (name "Net-(E20A-O)") (class "Default")
      (node (ref "E20") (pin "2") (pinfunction "O_2") (pintype "output"))
      (node (ref "E23") (pin "3") (pinfunction "CLK_3") (pintype "input"))
    )
    (net (code "100") (name "Net-(E20F-I)") (class "Default")
      (node (ref "E20") (pin "13") (pinfunction "I_13") (pintype "input"))
      (node (ref "E21") (pin "8") (pinfunction "O_8") (pintype "output"))
      (node (ref "E23") (pin "2") (pinfunction "D_2") (pintype "input"))
    )
    (net (code "101") (name "Net-(E20F-O)") (class "Default")
      (node (ref "E20") (pin "12") (pinfunction "O_12") (pintype "output"))
      (node (ref "E24") (pin "1") (pinfunction "SER_1") (pintype "input"))
    )
    (net (code "102") (name "Net-(E21A-I0)") (class "Default")
      (node (ref "E21") (pin "1") (pinfunction "I0_1") (pintype "input"))
      (node (ref "E24") (pin "13") (pinfunction "QA_13") (pintype "output"))
    )
    (net (code "103") (name "Net-(E21A-I1)") (class "Default")
      (node (ref "E21") (pin "2") (pinfunction "I1_2") (pintype "input"))
      (node (ref "E24") (pin "12") (pinfunction "QB_12") (pintype "output"))
    )
    (net (code "104") (name "Net-(E21A-I2)") (class "Default")
      (node (ref "E21") (pin "4") (pinfunction "I2_4") (pintype "input"))
      (node (ref "E24") (pin "11") (pinfunction "QC_11") (pintype "output"))
    )
    (net (code "105") (name "Net-(E21A-O)") (class "Default")
      (node (ref "E21") (pin "6") (pinfunction "O_6") (pintype "output"))
      (node (ref "E23") (pin "1") (pinfunction "CLR_1") (pintype "input"))
    )
    (net (code "106") (name "Net-(E22A-A)") (class "Default")
      (node (ref "E22") (pin "15") (pinfunction "A_15") (pintype "input"))
      (node (ref "E25") (pin "9") (pinfunction "QB_9") (pintype "output"))
    )
    (net (code "107") (name "Net-(E23A-Q)") (class "Default")
      (node (ref "E23") (pin "11") (pinfunction "CLK_11") (pintype "input"))
      (node (ref "E23") (pin "5") (pinfunction "Q_5") (pintype "output"))
    )
    (net (code "108") (name "Net-(E25A-CKB)") (class "Default")
      (node (ref "E25") (pin "1") (pinfunction "CKB_1") (pintype "input"))
      (node (ref "E25") (pin "12") (pinfunction "QA_12") (pintype "output"))
    )
    (net (code "109") (name "Net-(Q1-B)") (class "Default")
      (node (ref "Q1") (pin "2") (pinfunction "B_2") (pintype "passive"))
      (node (ref "R38") (pin "1") (pinfunction "1_1") (pintype "passive"))
    )
    (net (code "110") (name "Net-(Q1-C)") (class "Default")
      (node (ref "Q1") (pin "3") (pinfunction "C_3") (pintype "passive"))
      (node (ref "R33") (pin "1") (pinfunction "1_1") (pintype "passive"))
    )
    (net (code "111") (name "Net-(Q1-E)") (class "Default")
      (node (ref "E15") (pin "3") (pinfunction "CA_3") (pintype "passive"))
      (node (ref "E15") (pin "8") (pinfunction "CA_8") (pintype "passive"))
      (node (ref "Q1") (pin "1") (pinfunction "E_1") (pintype "passive"))
    )
    (net (code "112") (name "Net-(Q2-B)") (class "Default")
      (node (ref "Q2") (pin "2") (pinfunction "B_2") (pintype "passive"))
      (node (ref "R37") (pin "1") (pinfunction "1_1") (pintype "passive"))
    )
    (net (code "113") (name "Net-(Q2-C)") (class "Default")
      (node (ref "Q2") (pin "3") (pinfunction "C_3") (pintype "passive"))
      (node (ref "R29") (pin "1") (pinfunction "1_1") (pintype "passive"))
    )
    (net (code "114") (name "Net-(Q2-E)") (class "Default")
      (node (ref "E3") (pin "3") (pinfunction "CA_3") (pintype "passive"))
      (node (ref "E3") (pin "8") (pinfunction "CA_8") (pintype "passive"))
      (node (ref "E9") (pin "3") (pinfunction "CA_3") (pintype "passive"))
      (node (ref "E9") (pin "8") (pinfunction "CA_8") (pintype "passive"))
      (node (ref "Q2") (pin "1") (pinfunction "E_1") (pintype "passive"))
    )
    (net (code "115") (name "Net-(Q3-B)") (class "Default")
      (node (ref "Q3") (pin "2") (pinfunction "B_2") (pintype "passive"))
      (node (ref "R36") (pin "1") (pinfunction "1_1") (pintype "passive"))
    )
    (net (code "116") (name "Net-(Q3-C)") (class "Default")
      (node (ref "Q3") (pin "3") (pinfunction "C_3") (pintype "passive"))
      (node (ref "R30") (pin "1") (pinfunction "1_1") (pintype "passive"))
    )
    (net (code "117") (name "Net-(Q3-E)") (class "Default")
      (node (ref "E11") (pin "3") (pinfunction "CA_3") (pintype "passive"))
      (node (ref "E11") (pin "8") (pinfunction "CA_8") (pintype "passive"))
      (node (ref "E4") (pin "3") (pinfunction "CA_3") (pintype "passive"))
      (node (ref "E4") (pin "8") (pinfunction "CA_8") (pintype "passive"))
      (node (ref "Q3") (pin "1") (pinfunction "E_1") (pintype "passive"))
    )
    (net (code "118") (name "Net-(Q4-B)") (class "Default")
      (node (ref "Q4") (pin "2") (pinfunction "B_2") (pintype "passive"))
      (node (ref "R35") (pin "1") (pinfunction "1_1") (pintype "passive"))
    )
    (net (code "119") (name "Net-(Q4-C)") (class "Default")
      (node (ref "Q4") (pin "3") (pinfunction "C_3") (pintype "passive"))
      (node (ref "R31") (pin "1") (pinfunction "1_1") (pintype "passive"))
    )
    (net (code "120") (name "Net-(Q4-E)") (class "Default")
      (node (ref "E12") (pin "3") (pinfunction "CA_3") (pintype "passive"))
      (node (ref "E12") (pin "8") (pinfunction "CA_8") (pintype "passive"))
      (node (ref "E5") (pin "3") (pinfunction "CA_3") (pintype "passive"))
      (node (ref "E5") (pin "8") (pinfunction "CA_8") (pintype "passive"))
      (node (ref "Q4") (pin "1") (pinfunction "E_1") (pintype "passive"))
    )
    (net (code "121") (name "Net-(Q5-B)") (class "Default")
      (node (ref "Q5") (pin "2") (pinfunction "B_2") (pintype "passive"))
      (node (ref "R34") (pin "1") (pinfunction "1_1") (pintype "passive"))
    )
    (net (code "122") (name "Net-(Q5-C)") (class "Default")
      (node (ref "Q5") (pin "3") (pinfunction "C_3") (pintype "passive"))
      (node (ref "R32") (pin "1") (pinfunction "1_1") (pintype "passive"))
    )
    (net (code "123") (name "Net-(Q5-E)") (class "Default")
      (node (ref "E14") (pin "3") (pinfunction "CA_3") (pintype "passive"))
      (node (ref "E14") (pin "8") (pinfunction "CA_8") (pintype "passive"))
      (node (ref "E7") (pin "3") (pinfunction "CA_3") (pintype "passive"))
      (node (ref "E7") (pin "8") (pinfunction "CA_8") (pintype "passive"))
      (node (ref "Q5") (pin "1") (pinfunction "E_1") (pintype "passive"))
    )
    (net (code "124") (name "RUN") (class "Default")
      (node (ref "E2") (pin "2") (pinfunction "I1_2") (pintype "input"))
      (node (ref "R9") (pin "1") (pinfunction "1_1") (pintype "passive"))
      (node (ref "RUN") (pin "1") (pinfunction "S_1") (pintype "passive"))
      (node (ref "RUN") (pin "2") (pinfunction "S1_2") (pintype "passive"))
    )
    (net (code "125") (name "VCC") (class "Default")
      (node (ref "C1") (pin "1") (pinfunction "1_1") (pintype "passive"))
      (node (ref "C10") (pin "1") (pinfunction "1_1") (pintype "passive"))
      (node (ref "C11") (pin "1") (pinfunction "1_1") (pintype "passive"))
      (node (ref "C12") (pin "1") (pinfunction "1_1") (pintype "passive"))
      (node (ref "C13") (pin "1") (pinfunction "1_1") (pintype "passive"))
      (node (ref "C14") (pin "1") (pinfunction "1_1") (pintype "passive"))
      (node (ref "C15") (pin "1") (pinfunction "1_1") (pintype "passive"))
      (node (ref "C16") (pin "1") (pinfunction "1_1") (pintype "passive"))
      (node (ref "C19") (pin "+") (pinfunction "+_+") (pintype "passive"))
      (node (ref "C2") (pin "1") (pinfunction "1_1") (pintype "passive"))
      (node (ref "C20") (pin "+") (pinfunction "+_+") (pintype "passive"))
      (node (ref "C3") (pin "1") (pinfunction "1_1") (pintype "passive"))
      (node (ref "C4") (pin "1") (pinfunction "1_1") (pintype "passive"))
      (node (ref "C5") (pin "1") (pinfunction "1_1") (pintype "passive"))
      (node (ref "C6") (pin "1") (pinfunction "1_1") (pintype "passive"))
      (node (ref "C7") (pin "1") (pinfunction "1_1") (pintype "passive"))
      (node (ref "C8") (pin "1") (pinfunction "1_1") (pintype "passive"))
      (node (ref "C9") (pin "1") (pinfunction "1_1") (pintype "passive"))
      (node (ref "E13") (pin "3") (pinfunction "LT_3") (pintype "input"))
      (node (ref "E13") (pin "4") (pinfunction "BI/RBO_4") (pintype "input"))
      (node (ref "E13") (pin "5") (pinfunction "RBI_5") (pintype "input"))
      (node (ref "E16") (pin "3") (pinfunction "LT_3") (pintype "input"))
      (node (ref "E16") (pin "4") (pinfunction "BI/RBO_4") (pintype "input"))
      (node (ref "E16") (pin "5") (pinfunction "RBI_5") (pintype "input"))
      (node (ref "E18") (pin "3") (pinfunction "CLR_3") (pintype "input"))
      (node (ref "E23") (pin "10") (pinfunction "PRE_10") (pintype "input"))
      (node (ref "E23") (pin "12") (pinfunction "D_12") (pintype "input"))
      (node (ref "E23") (pin "4") (pinfunction "PRE_4") (pintype "input"))
      (node (ref "E24") (pin "2") (pinfunction "A_2") (pintype "input"))
      (node (ref "E24") (pin "3") (pinfunction "B_3") (pintype "input"))
      (node (ref "E24") (pin "4") (pinfunction "C_4") (pintype "input"))
      (node (ref "E24") (pin "5") (pinfunction "D_5") (pintype "input"))
      (node (ref "E24") (pin "8") (pinfunction "CK2_8") (pintype "input"))
      (node (ref "E8") (pin "3") (pinfunction "LT_3") (pintype "input"))
      (node (ref "E8") (pin "4") (pinfunction "BI/RBO_4") (pintype "input"))
      (node (ref "E8") (pin "5") (pinfunction "RBI_5") (pintype "input"))
      (node (ref "J1") (pin "16") (pinfunction "16_16") (pintype "passive"))
      (node (ref "J2") (pin "16") (pinfunction "16_16") (pintype "passive"))
      (node (ref "R1") (pin "2") (pinfunction "2_2") (pintype "passive"))
      (node (ref "R10") (pin "2") (pinfunction "2_2") (pintype "passive"))
      (node (ref "R11") (pin "2") (pinfunction "2_2") (pintype "passive"))
      (node (ref "R12") (pin "2") (pinfunction "2_2") (pintype "passive"))
      (node (ref "R13") (pin "2") (pinfunction "2_2") (pintype "passive"))
      (node (ref "R14") (pin "2") (pinfunction "2_2") (pintype "passive"))
      (node (ref "R15") (pin "2") (pinfunction "2_2") (pintype "passive"))
      (node (ref "R16") (pin "2") (pinfunction "2_2") (pintype "passive"))
      (node (ref "R17") (pin "2") (pinfunction "2_2") (pintype "passive"))
      (node (ref "R18") (pin "2") (pinfunction "2_2") (pintype "passive"))
      (node (ref "R19") (pin "2") (pinfunction "2_2") (pintype "passive"))
      (node (ref "R2") (pin "1") (pinfunction "1_1") (pintype "passive"))
      (node (ref "R20") (pin "2") (pinfunction "2_2") (pintype "passive"))
      (node (ref "R21") (pin "2") (pinfunction "2_2") (pintype "passive"))
      (node (ref "R22") (pin "2") (pinfunction "2_2") (pintype "passive"))
      (node (ref "R23") (pin "2") (pinfunction "2_2") (pintype "passive"))
      (node (ref "R24") (pin "2") (pinfunction "2_2") (pintype "passive"))
      (node (ref "R25") (pin "2") (pinfunction "2_2") (pintype "passive"))
      (node (ref "R26") (pin "2") (pinfunction "2_2") (pintype "passive"))
      (node (ref "R27") (pin "2") (pinfunction "2_2") (pintype "passive"))
      (node (ref "R28") (pin "2") (pinfunction "2_2") (pintype "passive"))
      (node (ref "R29") (pin "2") (pinfunction "2_2") (pintype "passive"))
      (node (ref "R3") (pin "2") (pinfunction "2_2") (pintype "passive"))
      (node (ref "R30") (pin "2") (pinfunction "2_2") (pintype "passive"))
      (node (ref "R31") (pin "2") (pinfunction "2_2") (pintype "passive"))
      (node (ref "R32") (pin "2") (pinfunction "2_2") (pintype "passive"))
      (node (ref "R33") (pin "2") (pinfunction "2_2") (pintype "passive"))
      (node (ref "R39") (pin "2") (pinfunction "2_2") (pintype "passive"))
      (node (ref "R4") (pin "1") (pinfunction "1_1") (pintype "passive"))
      (node (ref "R40") (pin "2") (pinfunction "2_2") (pintype "passive"))
      (node (ref "R41") (pin "2") (pinfunction "2_2") (pintype "passive"))
      (node (ref "R42") (pin "2") (pinfunction "2_2") (pintype "passive"))
      (node (ref "R43") (pin "2") (pinfunction "2_2") (pintype "passive"))
      (node (ref "R44") (pin "2") (pinfunction "2_2") (pintype "passive"))
      (node (ref "R45") (pin "2") (pinfunction "2_2") (pintype "passive"))
      (node (ref "R46") (pin "2") (pinfunction "2_2") (pintype "passive"))
      (node (ref "R5") (pin "2") (pinfunction "2_2") (pintype "passive"))
      (node (ref "R6") (pin "2") (pinfunction "2_2") (pintype "passive"))
      (node (ref "R7") (pin "2") (pinfunction "2_2") (pintype "passive"))
      (node (ref "R8") (pin "2") (pinfunction "2_2") (pintype "passive"))
      (node (ref "R9") (pin "2") (pinfunction "2_2") (pintype "passive"))
      (node (ref "VCC") (pin "1") (pinfunction "P_1") (pintype "passive"))
    )
    (net (code "126") (name "unconnected-(E3-DP-Pad5)") (class "Default")
      (node (ref "E3") (pin "5") (pinfunction "DP_5") (pintype "passive"))
    )
    (net (code "127") (name "unconnected-(E4-DP-Pad5)") (class "Default")
      (node (ref "E4") (pin "5") (pinfunction "DP_5") (pintype "passive"))
    )
    (net (code "128") (name "unconnected-(E5-DP-Pad5)") (class "Default")
      (node (ref "E5") (pin "5") (pinfunction "DP_5") (pintype "passive"))
    )
    (net (code "129") (name "unconnected-(E6A-EO-Pad15)") (class "Default")
      (node (ref "E6") (pin "15") (pinfunction "EO_15") (pintype "output"))
    )
    (net (code "130") (name "unconnected-(E7-DP-Pad5)") (class "Default")
      (node (ref "E7") (pin "5") (pinfunction "DP_5") (pintype "passive"))
    )
    (net (code "131") (name "unconnected-(E9-DP-Pad5)") (class "Default")
      (node (ref "E9") (pin "5") (pinfunction "DP_5") (pintype "passive"))
    )
    (net (code "132") (name "unconnected-(E11-DP-Pad5)") (class "Default")
      (node (ref "E11") (pin "5") (pinfunction "DP_5") (pintype "passive"))
    )
    (net (code "133") (name "unconnected-(E12-DP-Pad5)") (class "Default")
      (node (ref "E12") (pin "5") (pinfunction "DP_5") (pintype "passive"))
    )
    (net (code "134") (name "unconnected-(E14-DP-Pad5)") (class "Default")
      (node (ref "E14") (pin "5") (pinfunction "DP_5") (pintype "passive"))
    )
    (net (code "135") (name "unconnected-(E15-DP-Pad5)") (class "Default")
      (node (ref "E15") (pin "5") (pinfunction "DP_5") (pintype "passive"))
    )
    (net (code "136") (name "unconnected-(E17A-7-Pad9)") (class "Default")
      (node (ref "E17") (pin "9") (pinfunction "7_9") (pintype "output"))
    )
    (net (code "137") (name "unconnected-(E17A-8-Pad10)") (class "Default")
      (node (ref "E17") (pin "10") (pinfunction "8_10") (pintype "output"))
    )
    (net (code "138") (name "unconnected-(E17A-9-Pad11)") (class "Default")
      (node (ref "E17") (pin "11") (pinfunction "9_11") (pintype "output"))
    )
    (net (code "139") (name "unconnected-(E18A-Q-Pad13)") (class "Default")
      (node (ref "E18") (pin "13") (pinfunction "Q_13") (pintype "output"))
    )
    (net (code "140") (name "unconnected-(E22A-O5-Pad6)") (class "Default")
      (node (ref "E22") (pin "6") (pinfunction "O5_6") (pintype "output"))
    )
    (net (code "141") (name "unconnected-(E22A-O6-Pad7)") (class "Default")
      (node (ref "E22") (pin "7") (pinfunction "O6_7") (pintype "output"))
    )
    (net (code "142") (name "unconnected-(E22A-O7-Pad9)") (class "Default")
      (node (ref "E22") (pin "9") (pinfunction "O7_9") (pintype "output"))
    )
    (net (code "143") (name "unconnected-(E22A-O8-Pad10)") (class "Default")
      (node (ref "E22") (pin "10") (pinfunction "O8_10") (pintype "output"))
    )
    (net (code "144") (name "unconnected-(E22A-O9-Pad11)") (class "Default")
      (node (ref "E22") (pin "11") (pinfunction "O9_11") (pintype "output"))
    )
    (net (code "145") (name "unconnected-(E23B-~{Q}-Pad8)") (class "Default")
      (node (ref "E23") (pin "8") (pinfunction "~{Q}_8") (pintype "output"))
    )
    (net (code "146") (name "~{EXTPUL}") (class "Default")
      (node (ref "E10") (pin "2") (pinfunction "I1_2") (pintype "input"))
      (node (ref "J2") (pin "9") (pinfunction "9_9") (pintype "passive"))
      (node (ref "R4") (pin "2") (pinfunction "2_2") (pintype "passive"))
    )
    (net (code "147") (name "~{FUN}") (class "Default")
      (node (ref "E21") (pin "12") (pinfunction "I2_12") (pintype "input"))
      (node (ref "E21") (pin "13") (pinfunction "I3_13") (pintype "input"))
      (node (ref "E6") (pin "14") (pinfunction "GS_14") (pintype "output"))
      (node (ref "J2") (pin "15") (pinfunction "15_15") (pintype "passive"))
    )
    (net (code "148") (name "~{KEY-F}") (class "Default")
      (node (ref "E23") (pin "6") (pinfunction "~{Q}_6") (pintype "output"))
      (node (ref "J2") (pin "3") (pinfunction "3_3") (pintype "passive"))
    )
    (net (code "149") (name "~{KFUN0}") (class "Default")
      (node (ref "E10") (pin "11") (pinfunction "O_11") (pintype "output"))
      (node (ref "J1") (pin "3") (pinfunction "3_3") (pintype "passive"))
    )
    (net (code "150") (name "~{KFUN1}") (class "Default")
      (node (ref "E10") (pin "8") (pinfunction "O_8") (pintype "output"))
      (node (ref "J1") (pin "2") (pinfunction "2_2") (pintype "passive"))
    )
    (net (code "151") (name "~{KFUN2}") (class "Default")
      (node (ref "E10") (pin "6") (pinfunction "O_6") (pintype "output"))
      (node (ref "J1") (pin "1") (pinfunction "1_1") (pintype "passive"))
    )
    (net (code "152") (name "~{MCLOCK}") (class "Default")
      (node (ref "E10") (pin "3") (pinfunction "O_3") (pintype "output"))
      (node (ref "E20") (pin "3") (pinfunction "I_3") (pintype "input"))
      (node (ref "E24") (pin "9") (pinfunction "CK1_9") (pintype "input"))
      (node (ref "J2") (pin "1") (pinfunction "1_1") (pintype "passive"))
    )
    (net (code "153") (name "~{SHLT}") (class "Default")
      (node (ref "!SHLT") (pin "1") (pinfunction "S_1") (pintype "passive"))
      (node (ref "!SHLT") (pin "2") (pinfunction "S1_2") (pintype "passive"))
      (node (ref "E2") (pin "1") (pinfunction "I0_1") (pintype "input"))
      (node (ref "J1") (pin "5") (pinfunction "5_5") (pintype "passive"))
      (node (ref "R19") (pin "1") (pinfunction "1_1") (pintype "passive"))
    )
    (net (code "154") (name "~{STHIS}") (class "Default")
      (node (ref "E2") (pin "6") (pinfunction "O_6") (pintype "output"))
      (node (ref "J1") (pin "4") (pinfunction "4_4") (pintype "passive"))
    )
  )
)
